# 20A-20.net
KiCad netlist of a schematic drawn in EAGLE
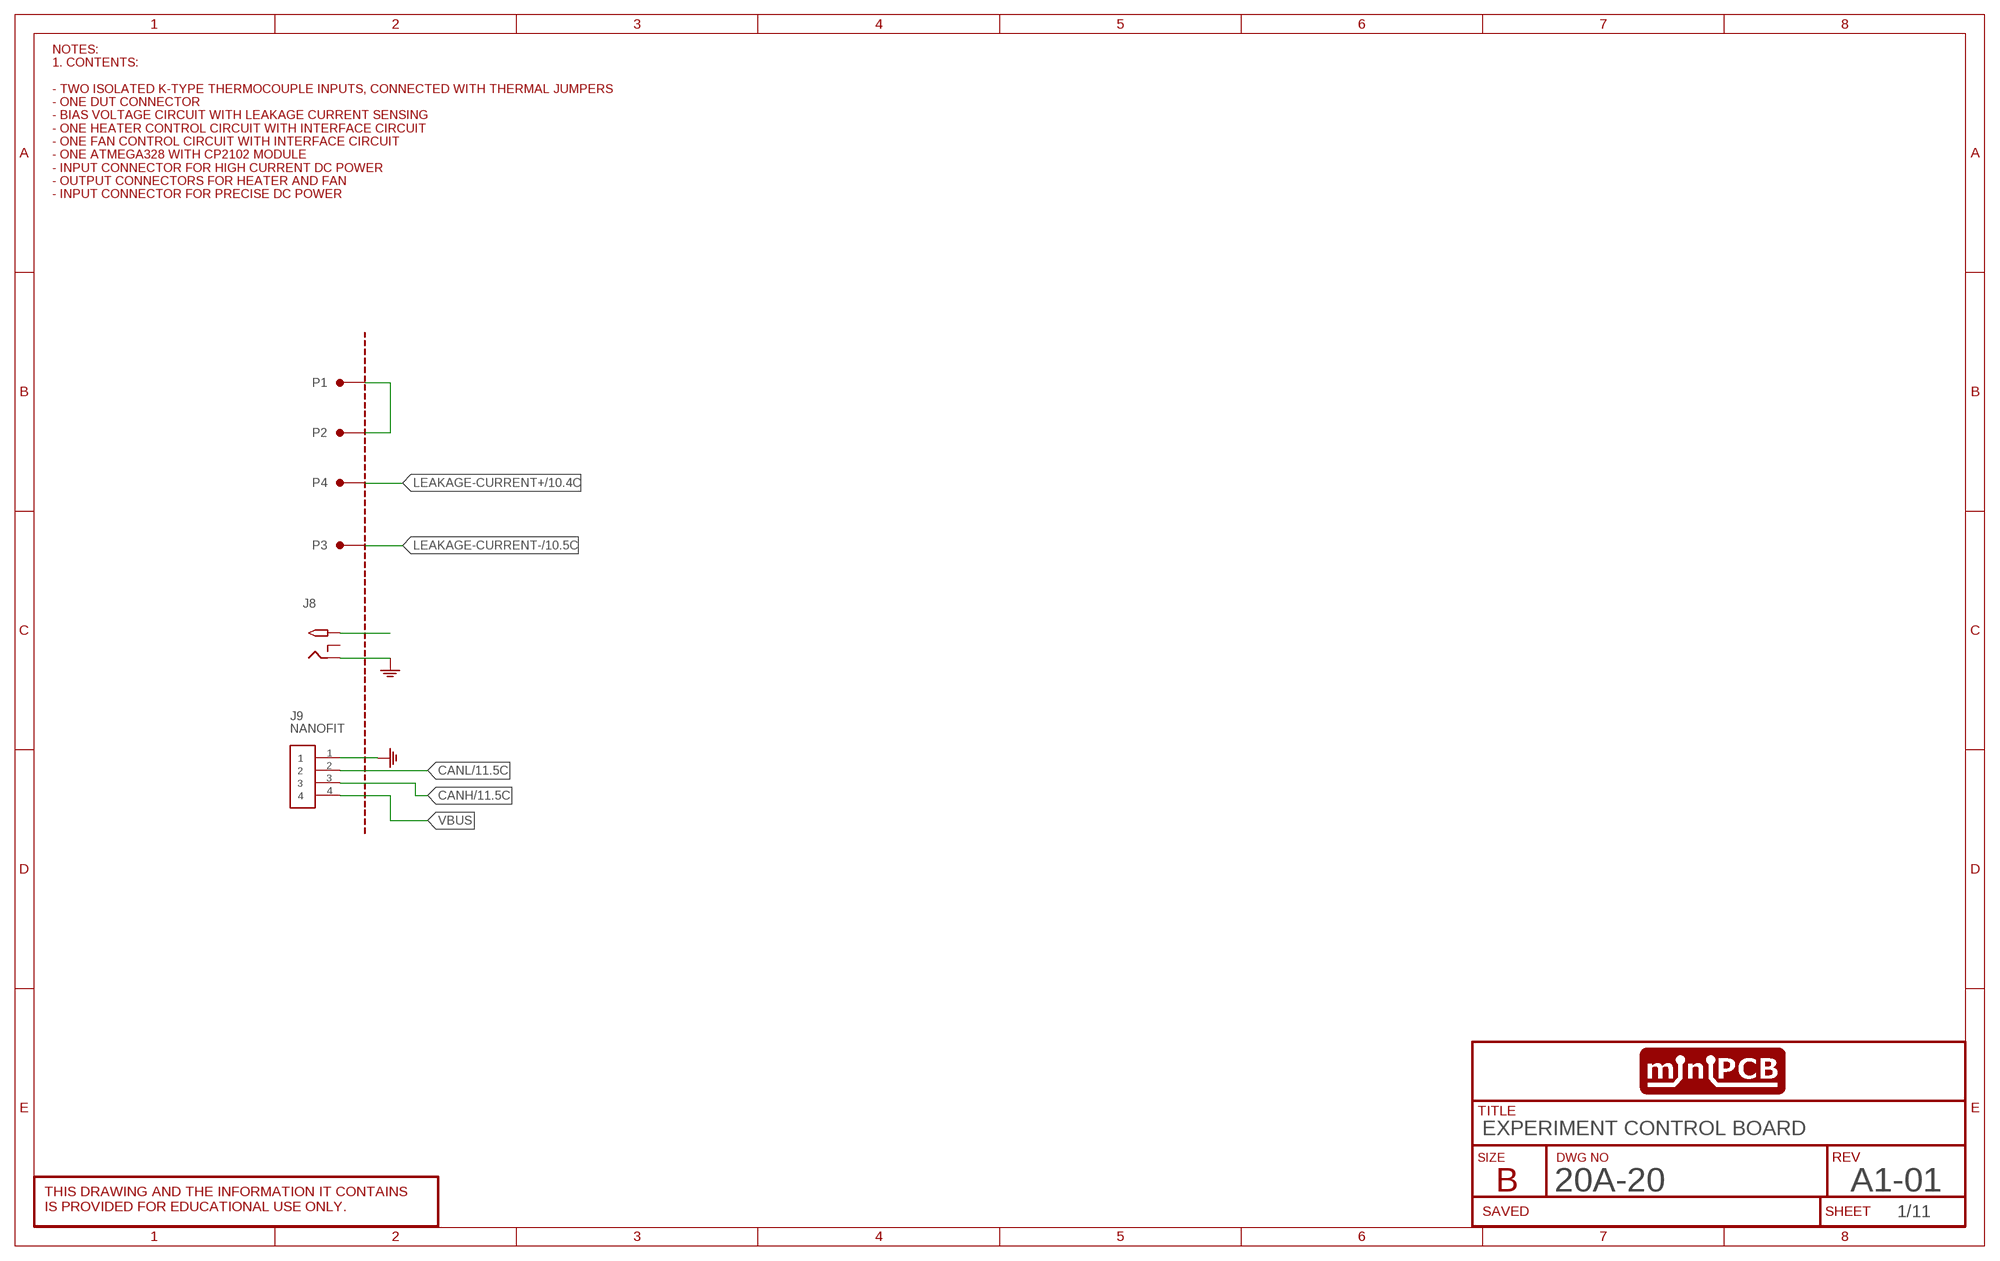
[diagram p0: schematic, sheet 1]
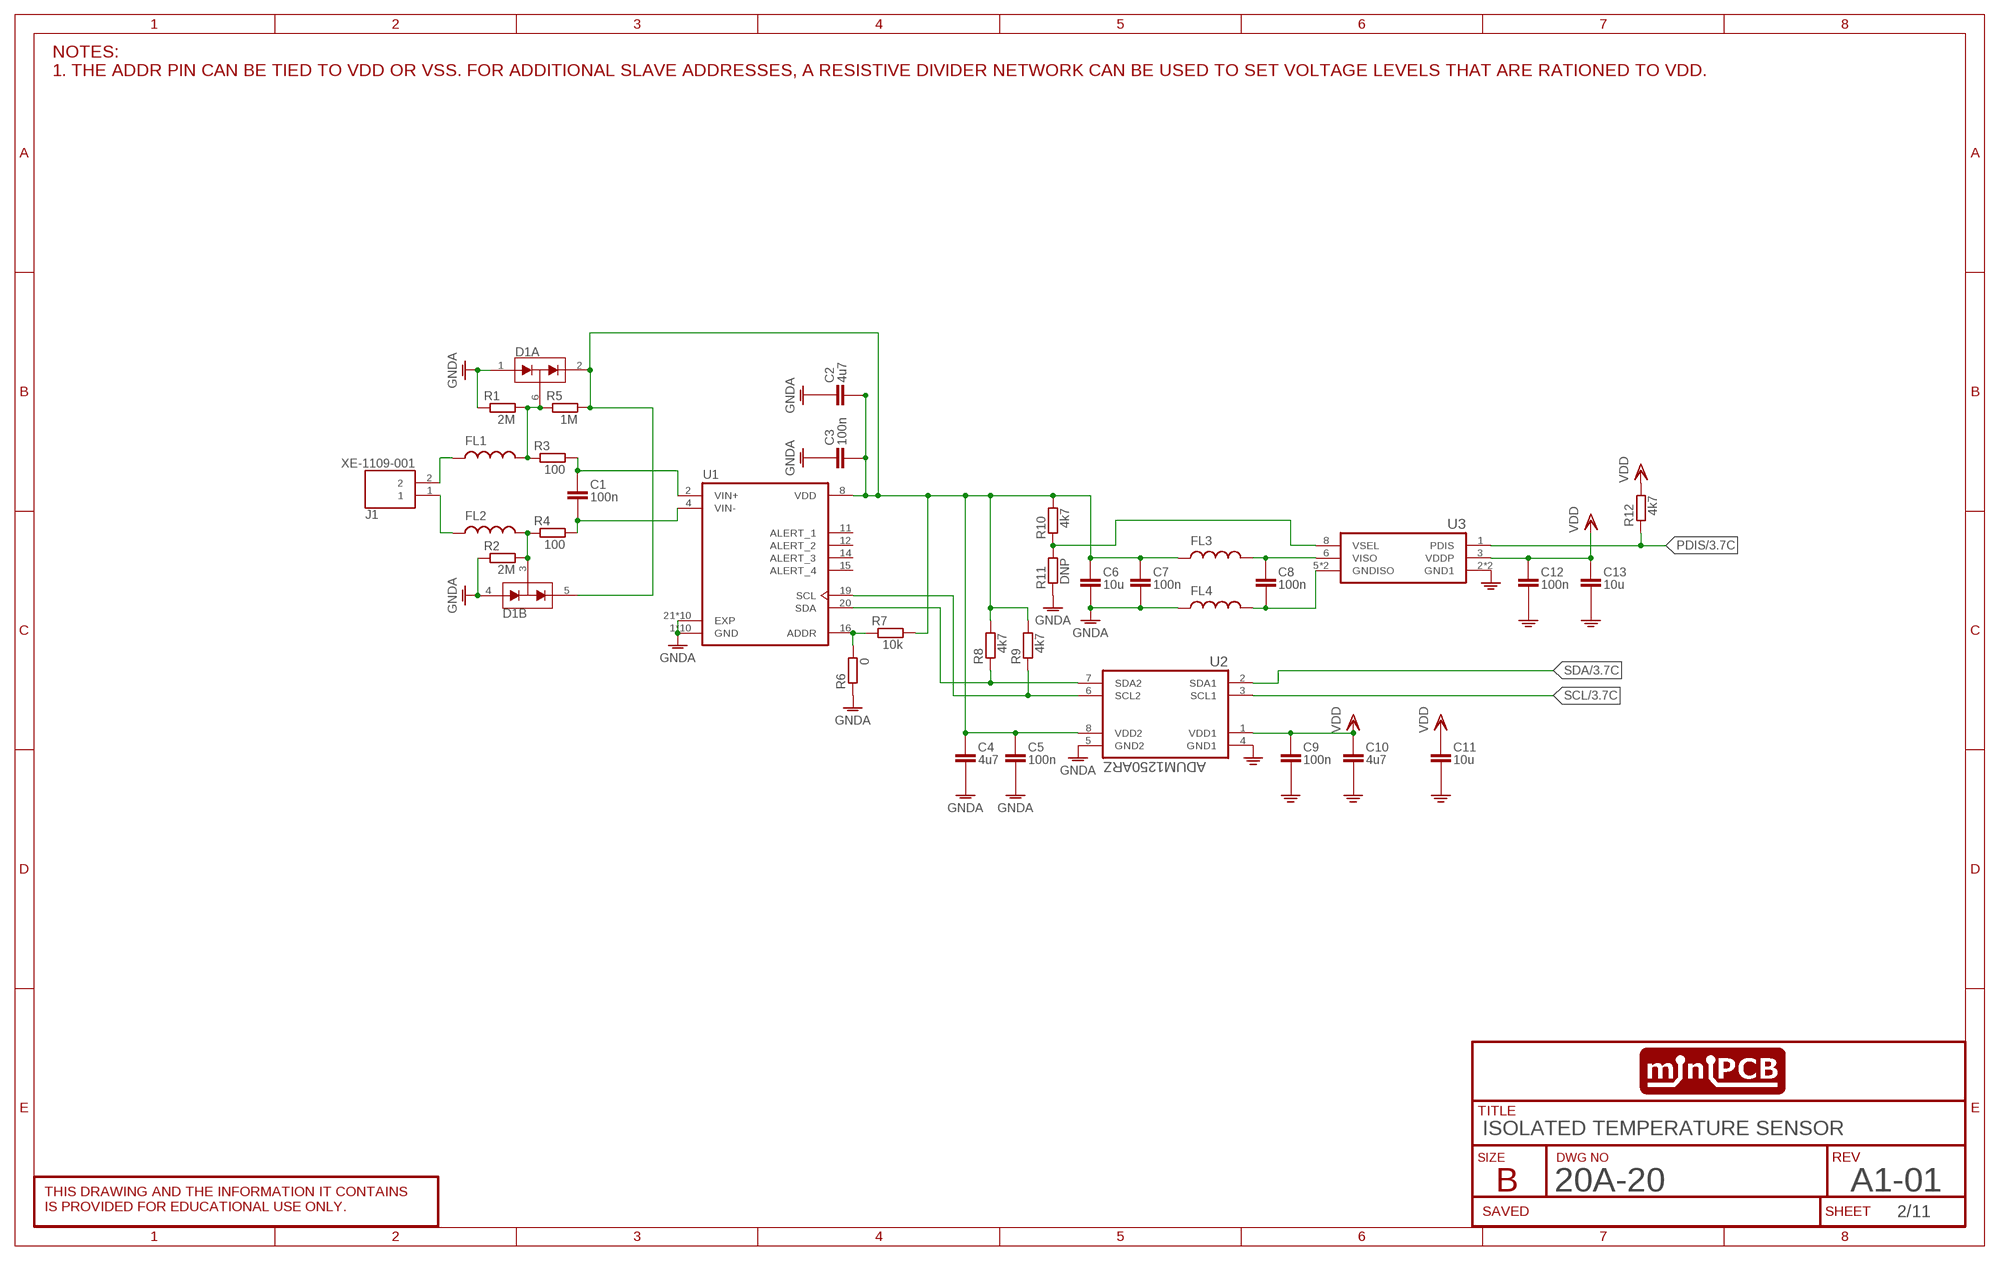
[diagram p1: schematic, sheet 2]
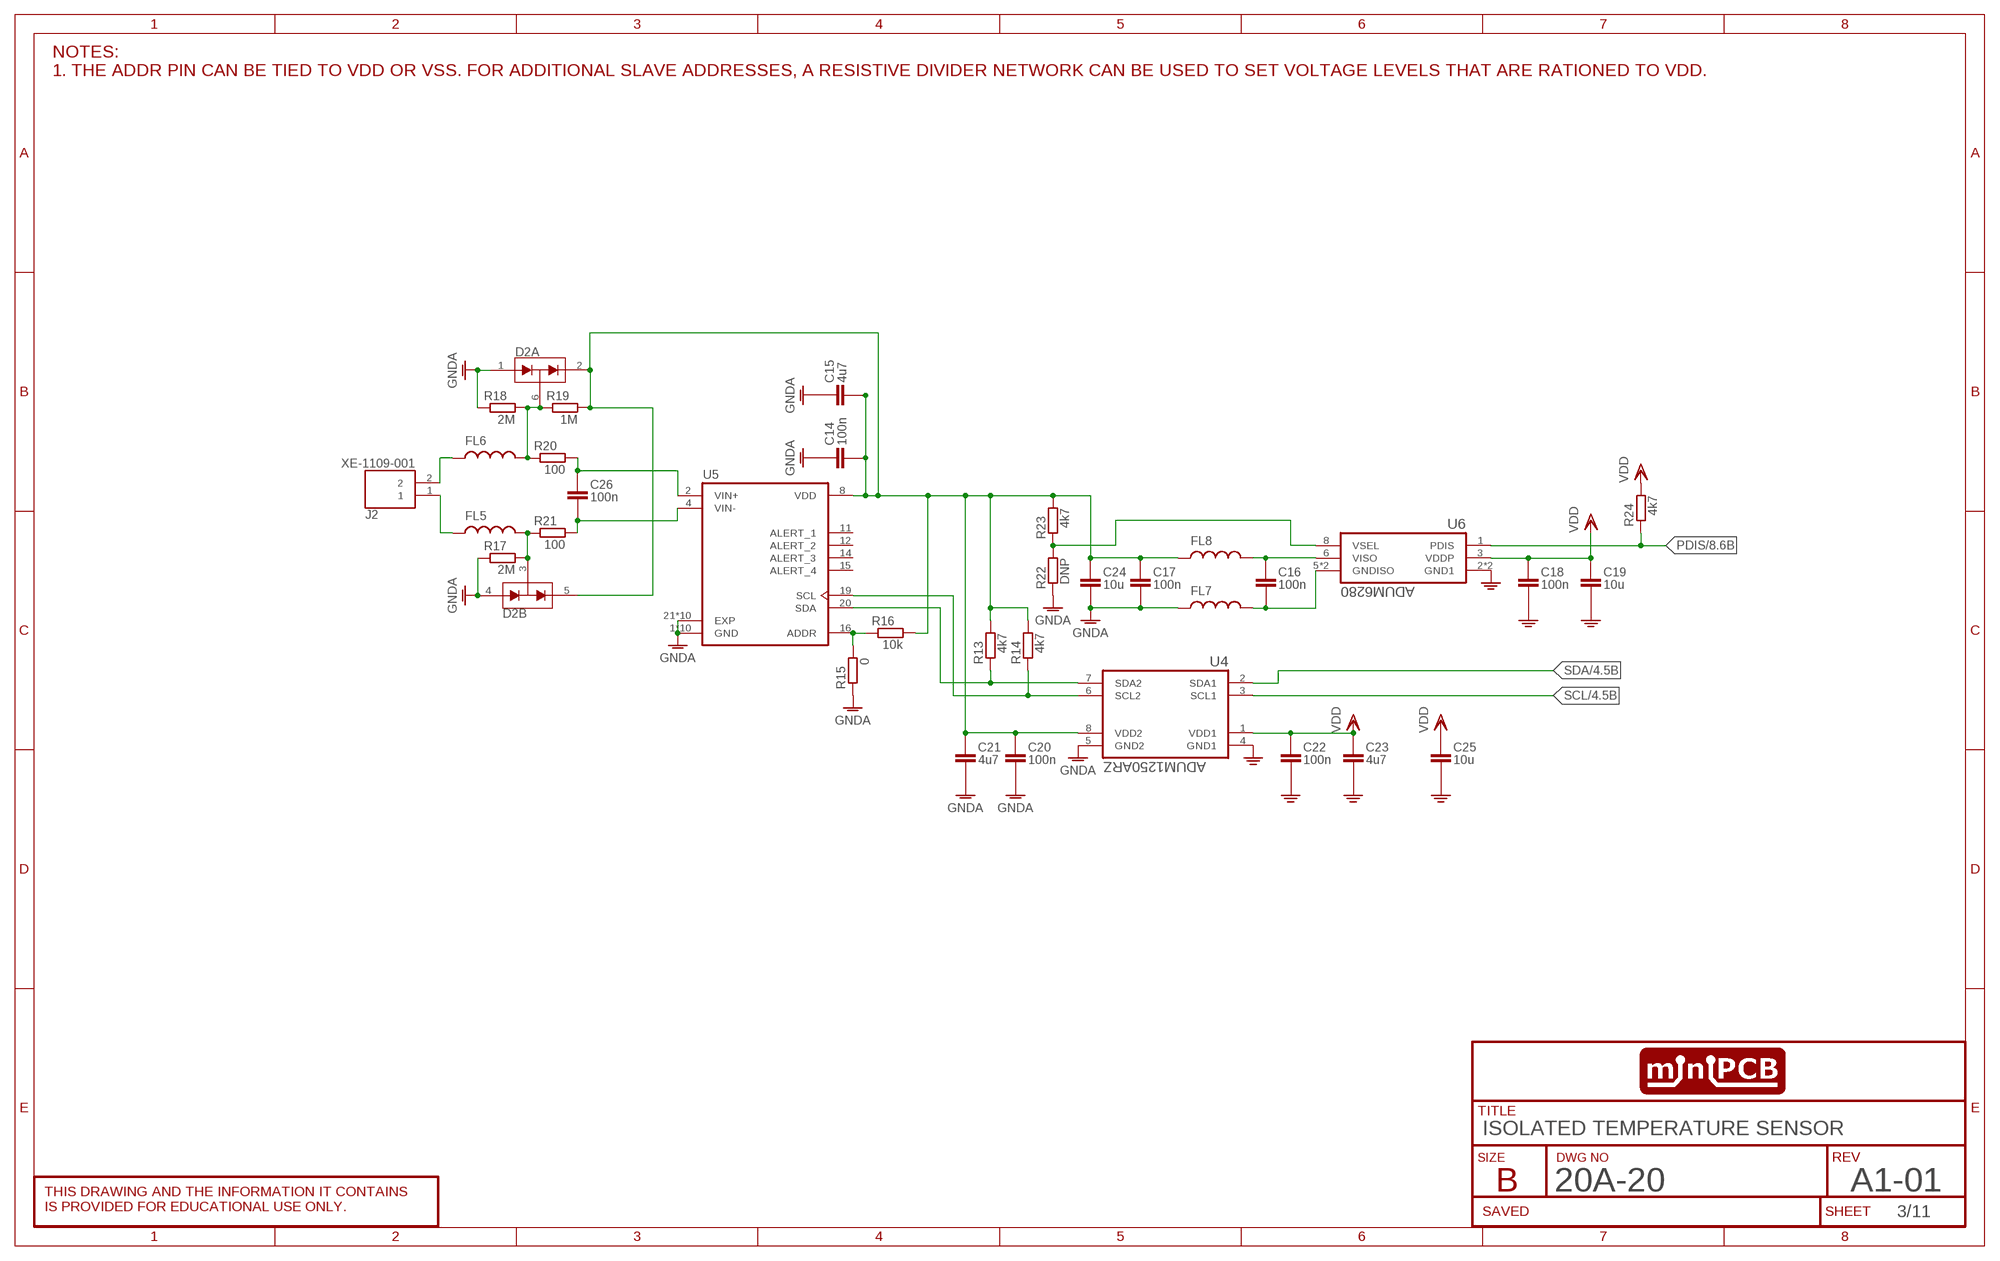
[diagram p2: schematic, sheet 3]
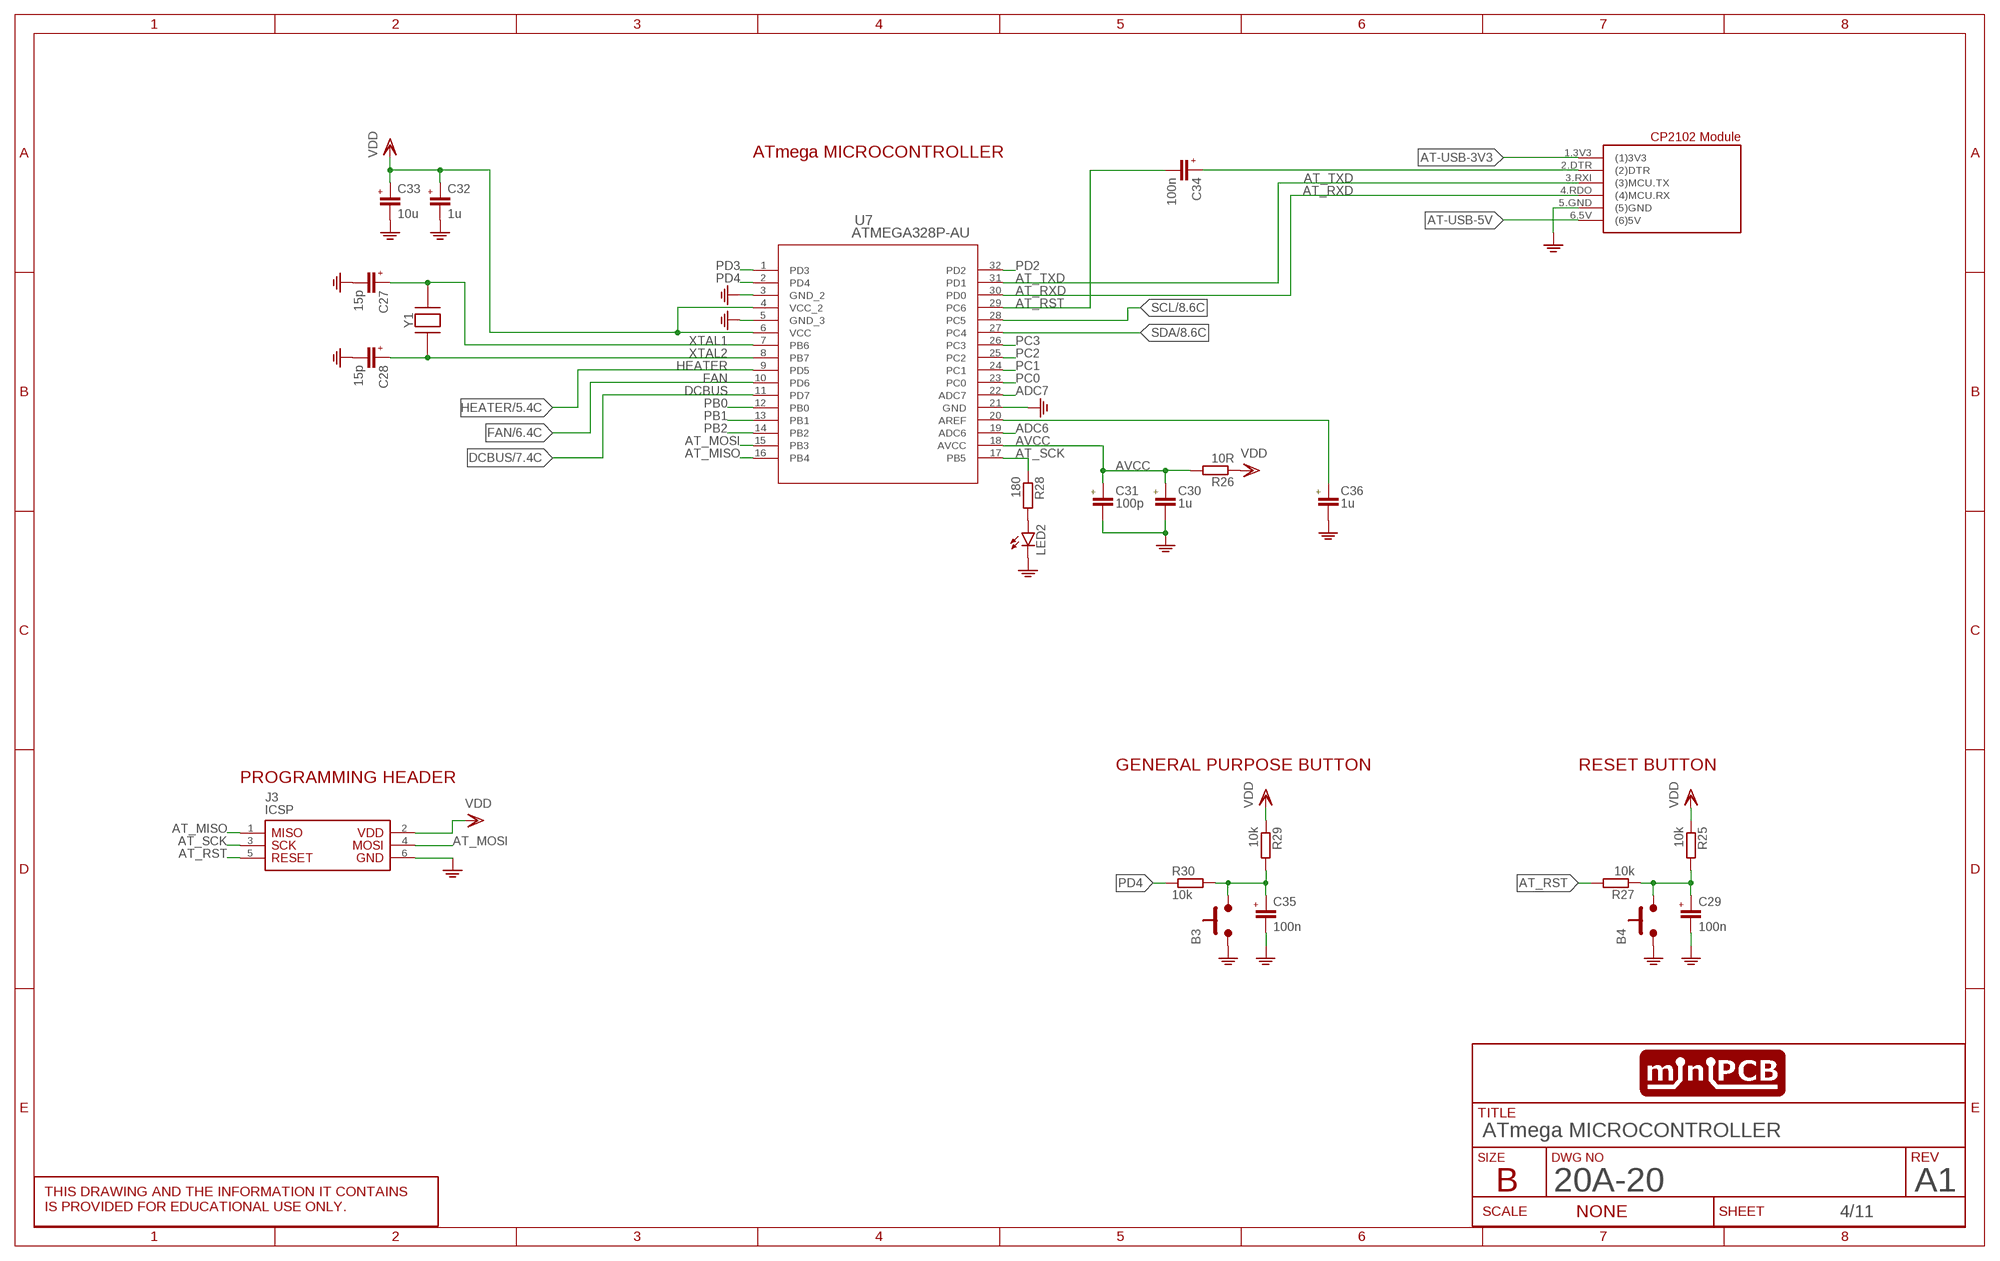
[diagram p3: schematic, sheet 4]
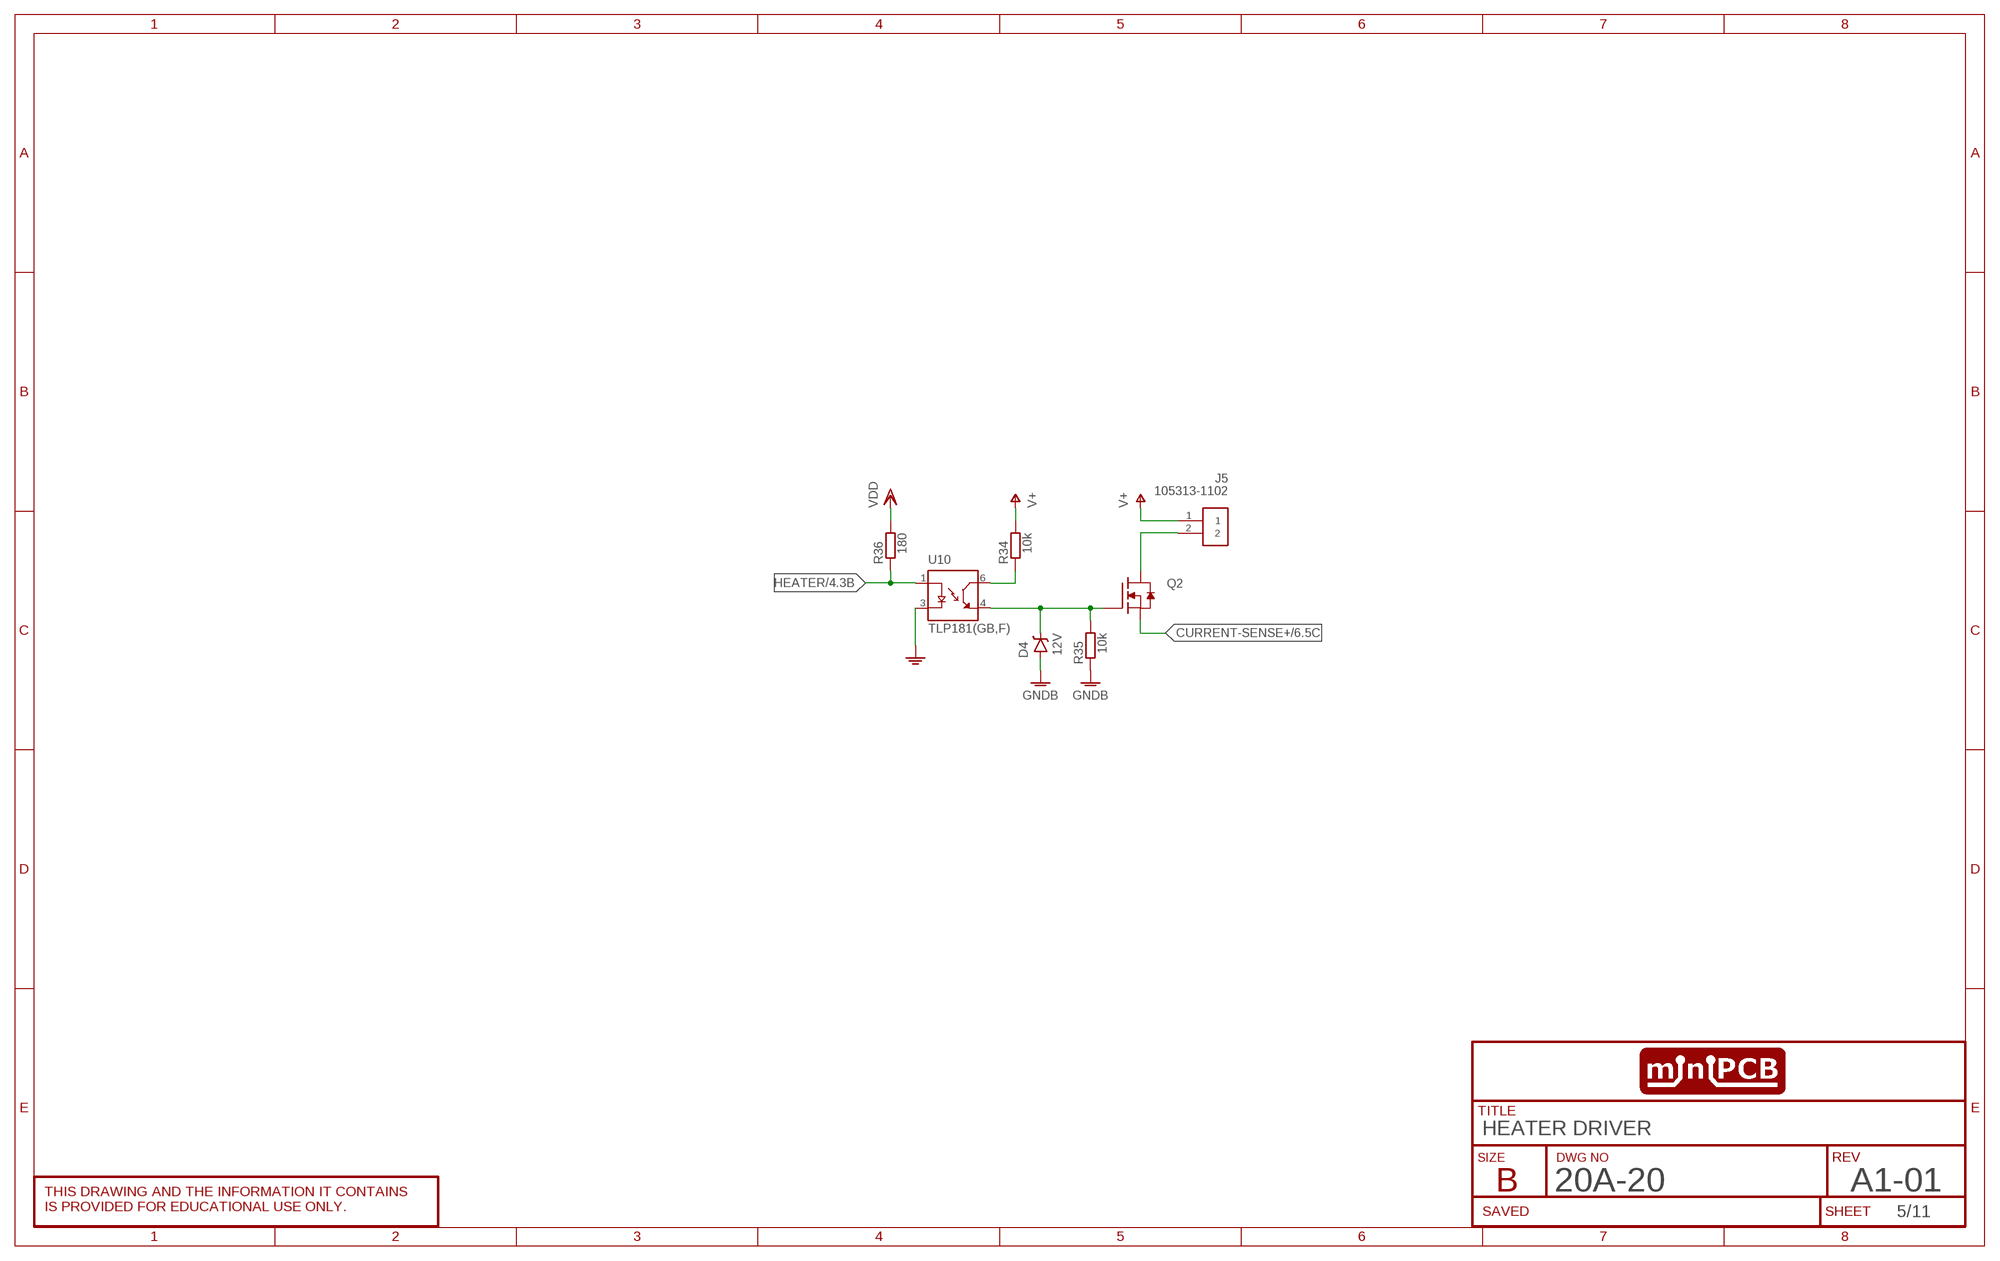
[diagram p4: schematic, sheet 5]
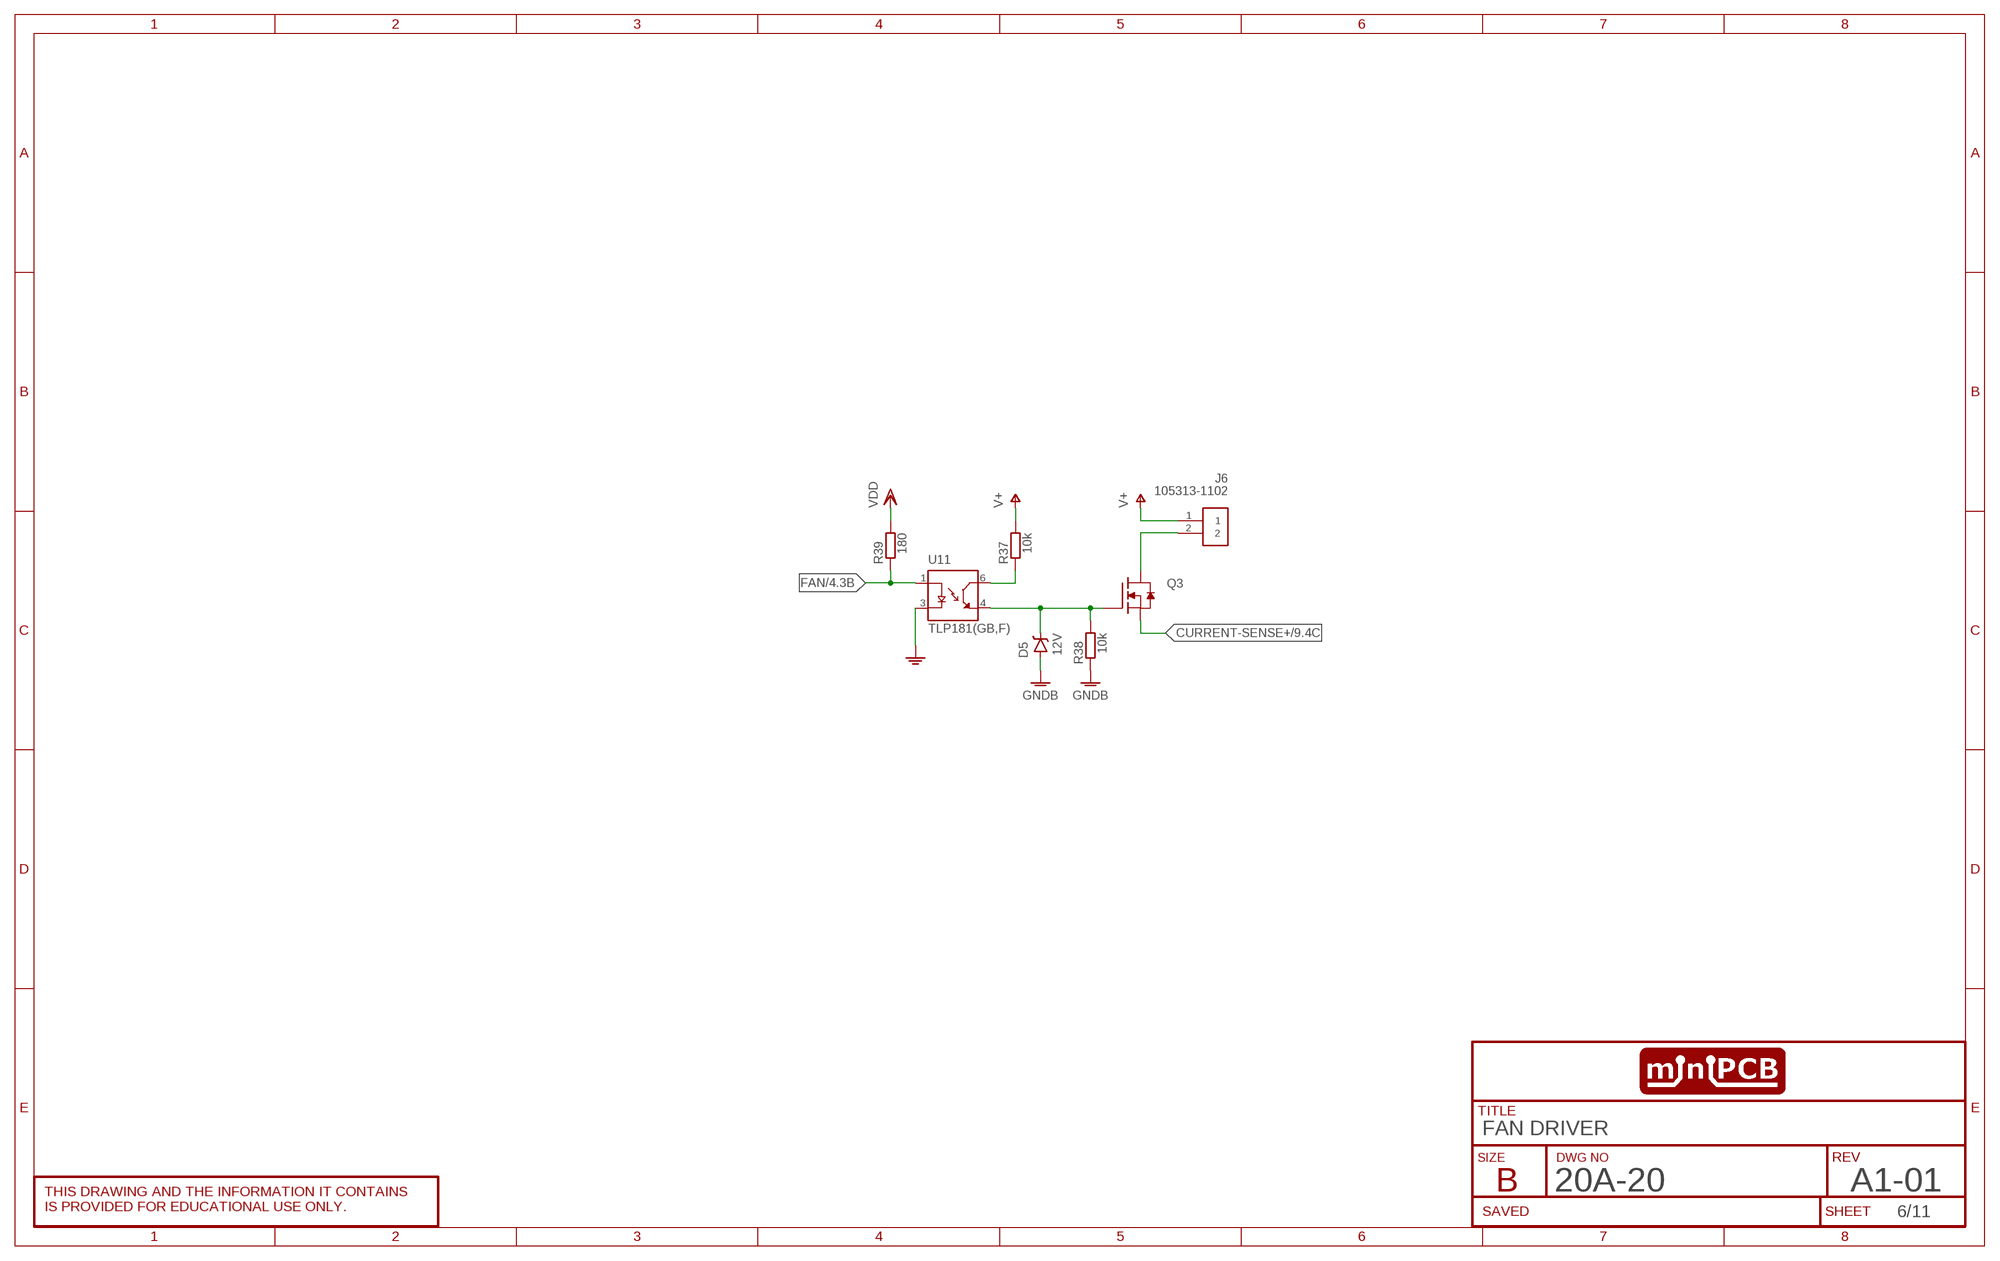
[diagram p5: schematic, sheet 6]
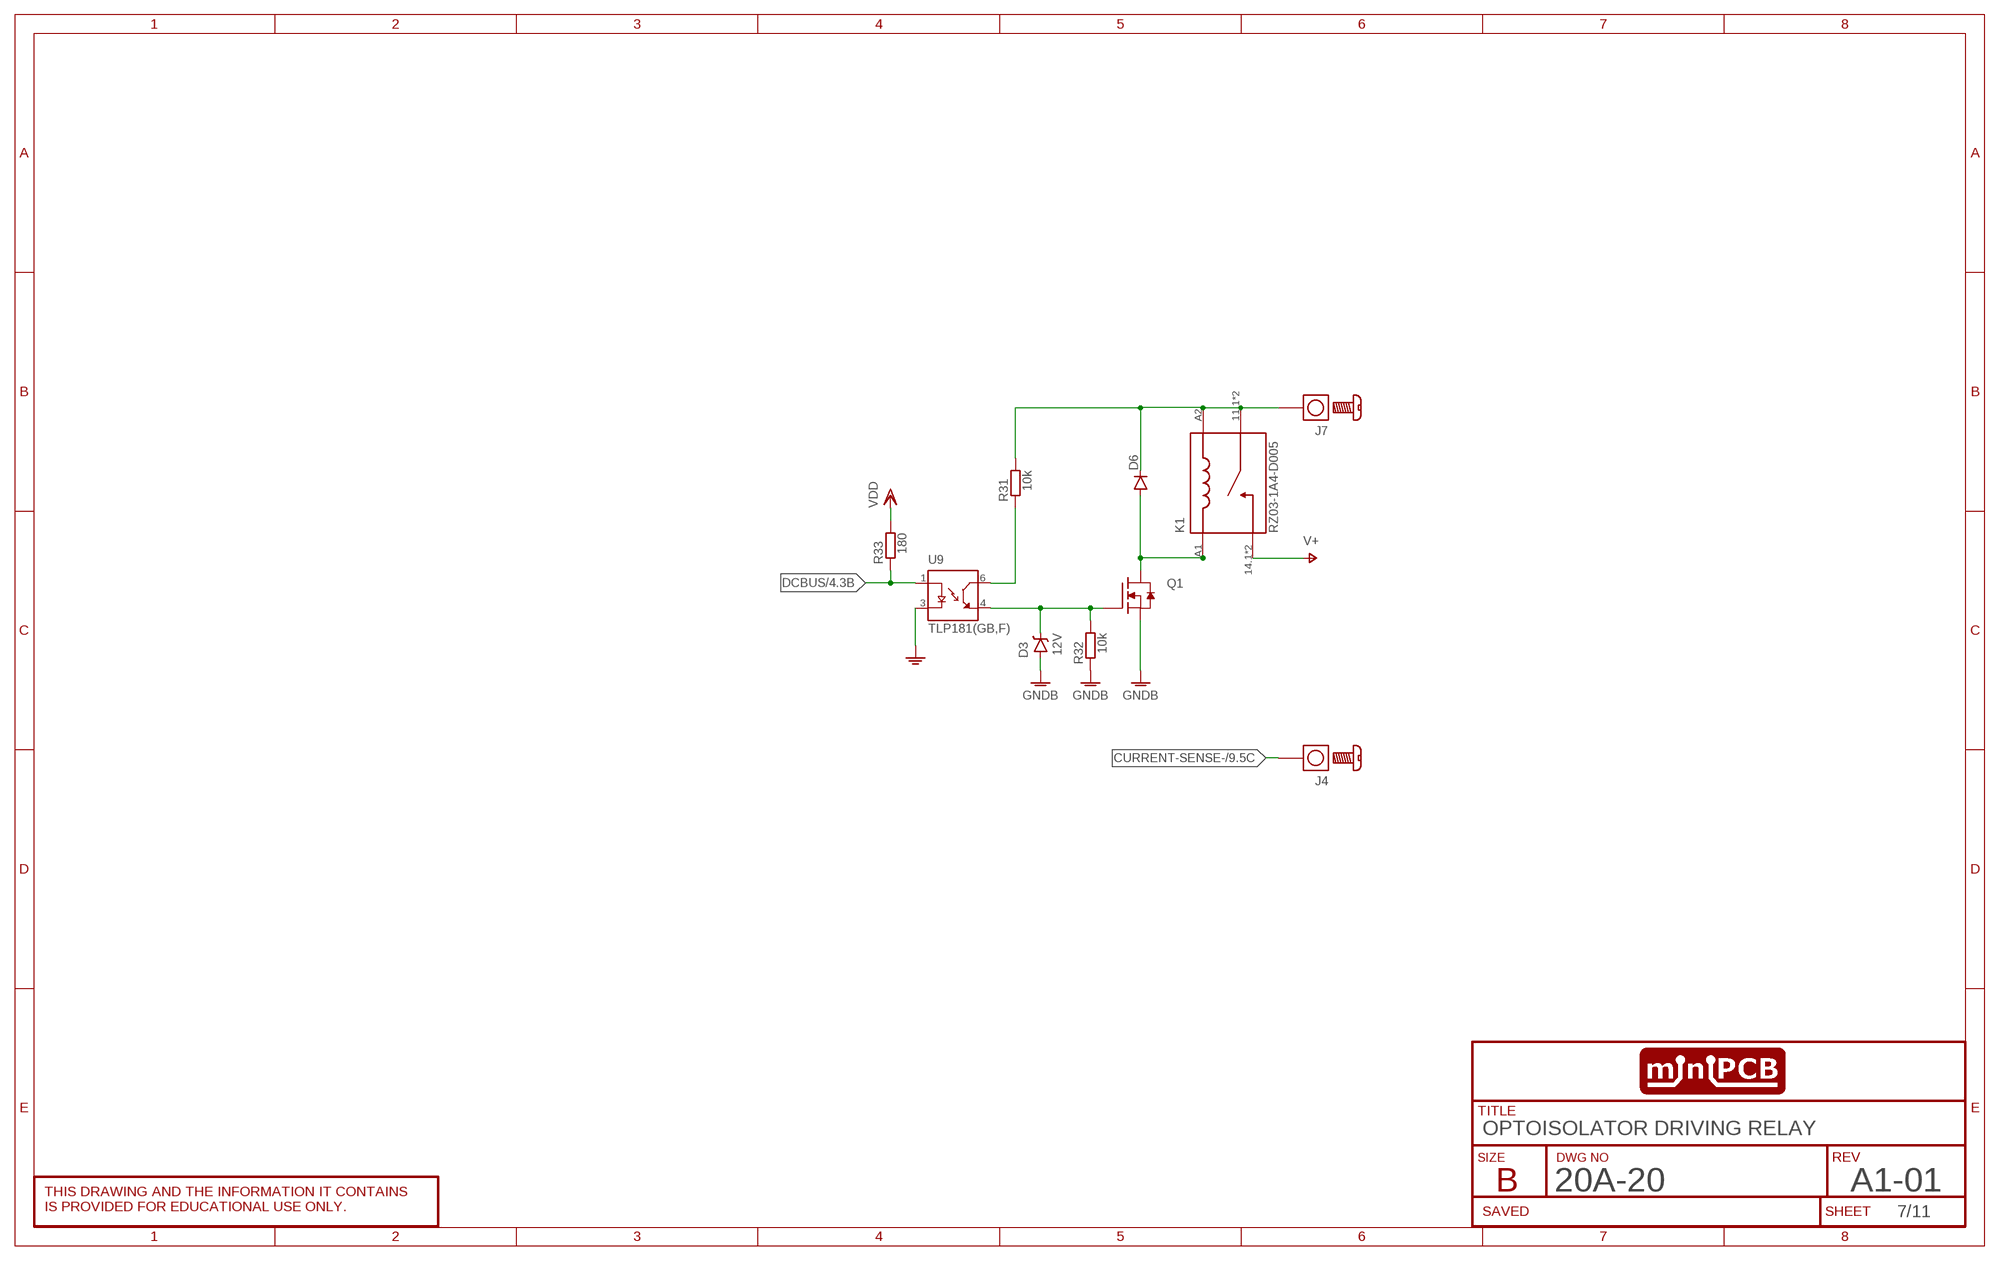
[diagram p6: schematic, sheet 7]
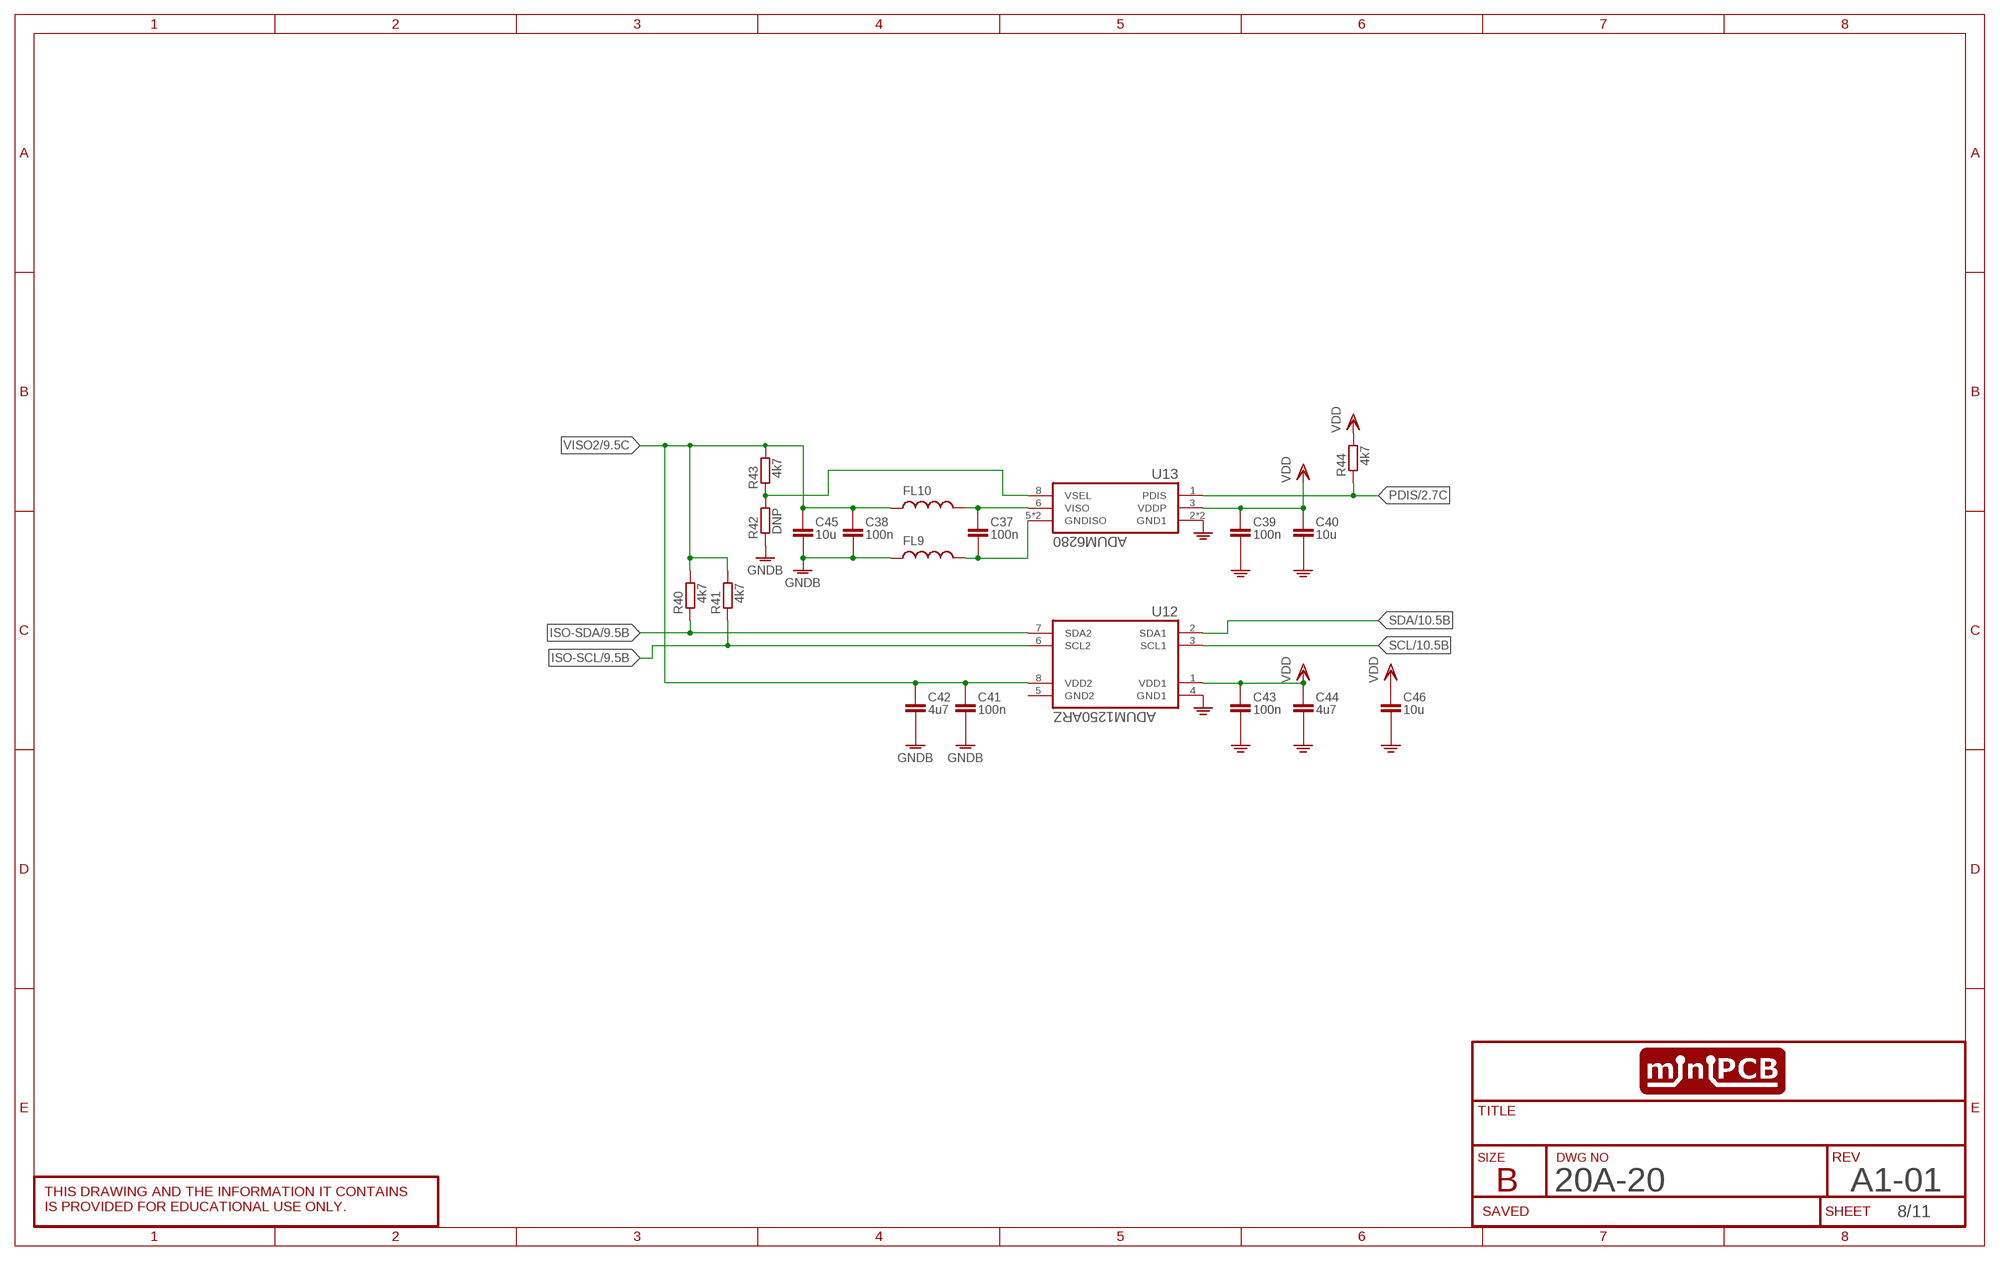
[diagram p7: schematic, sheet 8]
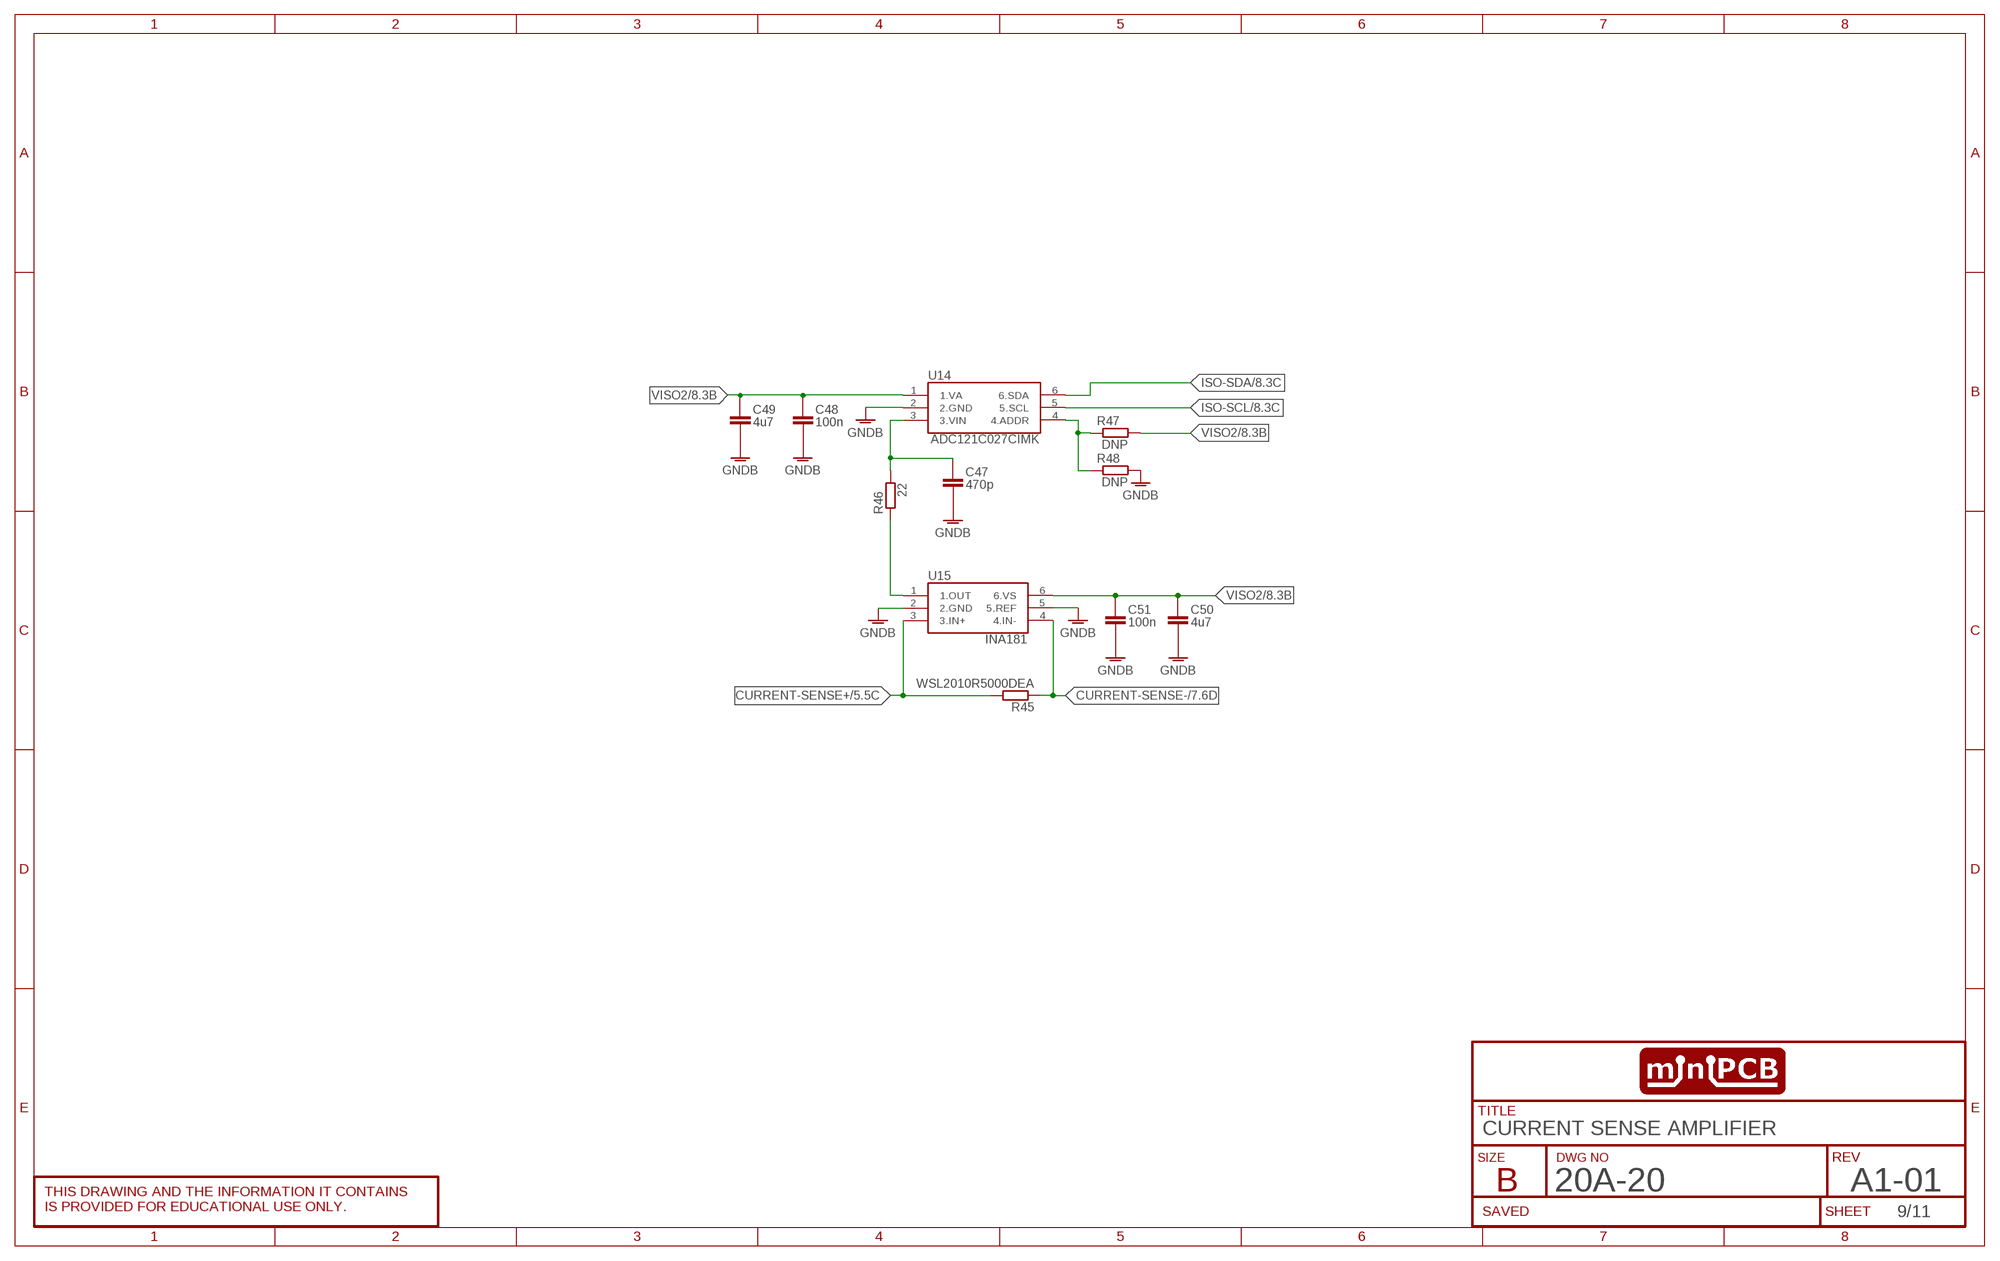
[diagram p8: schematic, sheet 9]
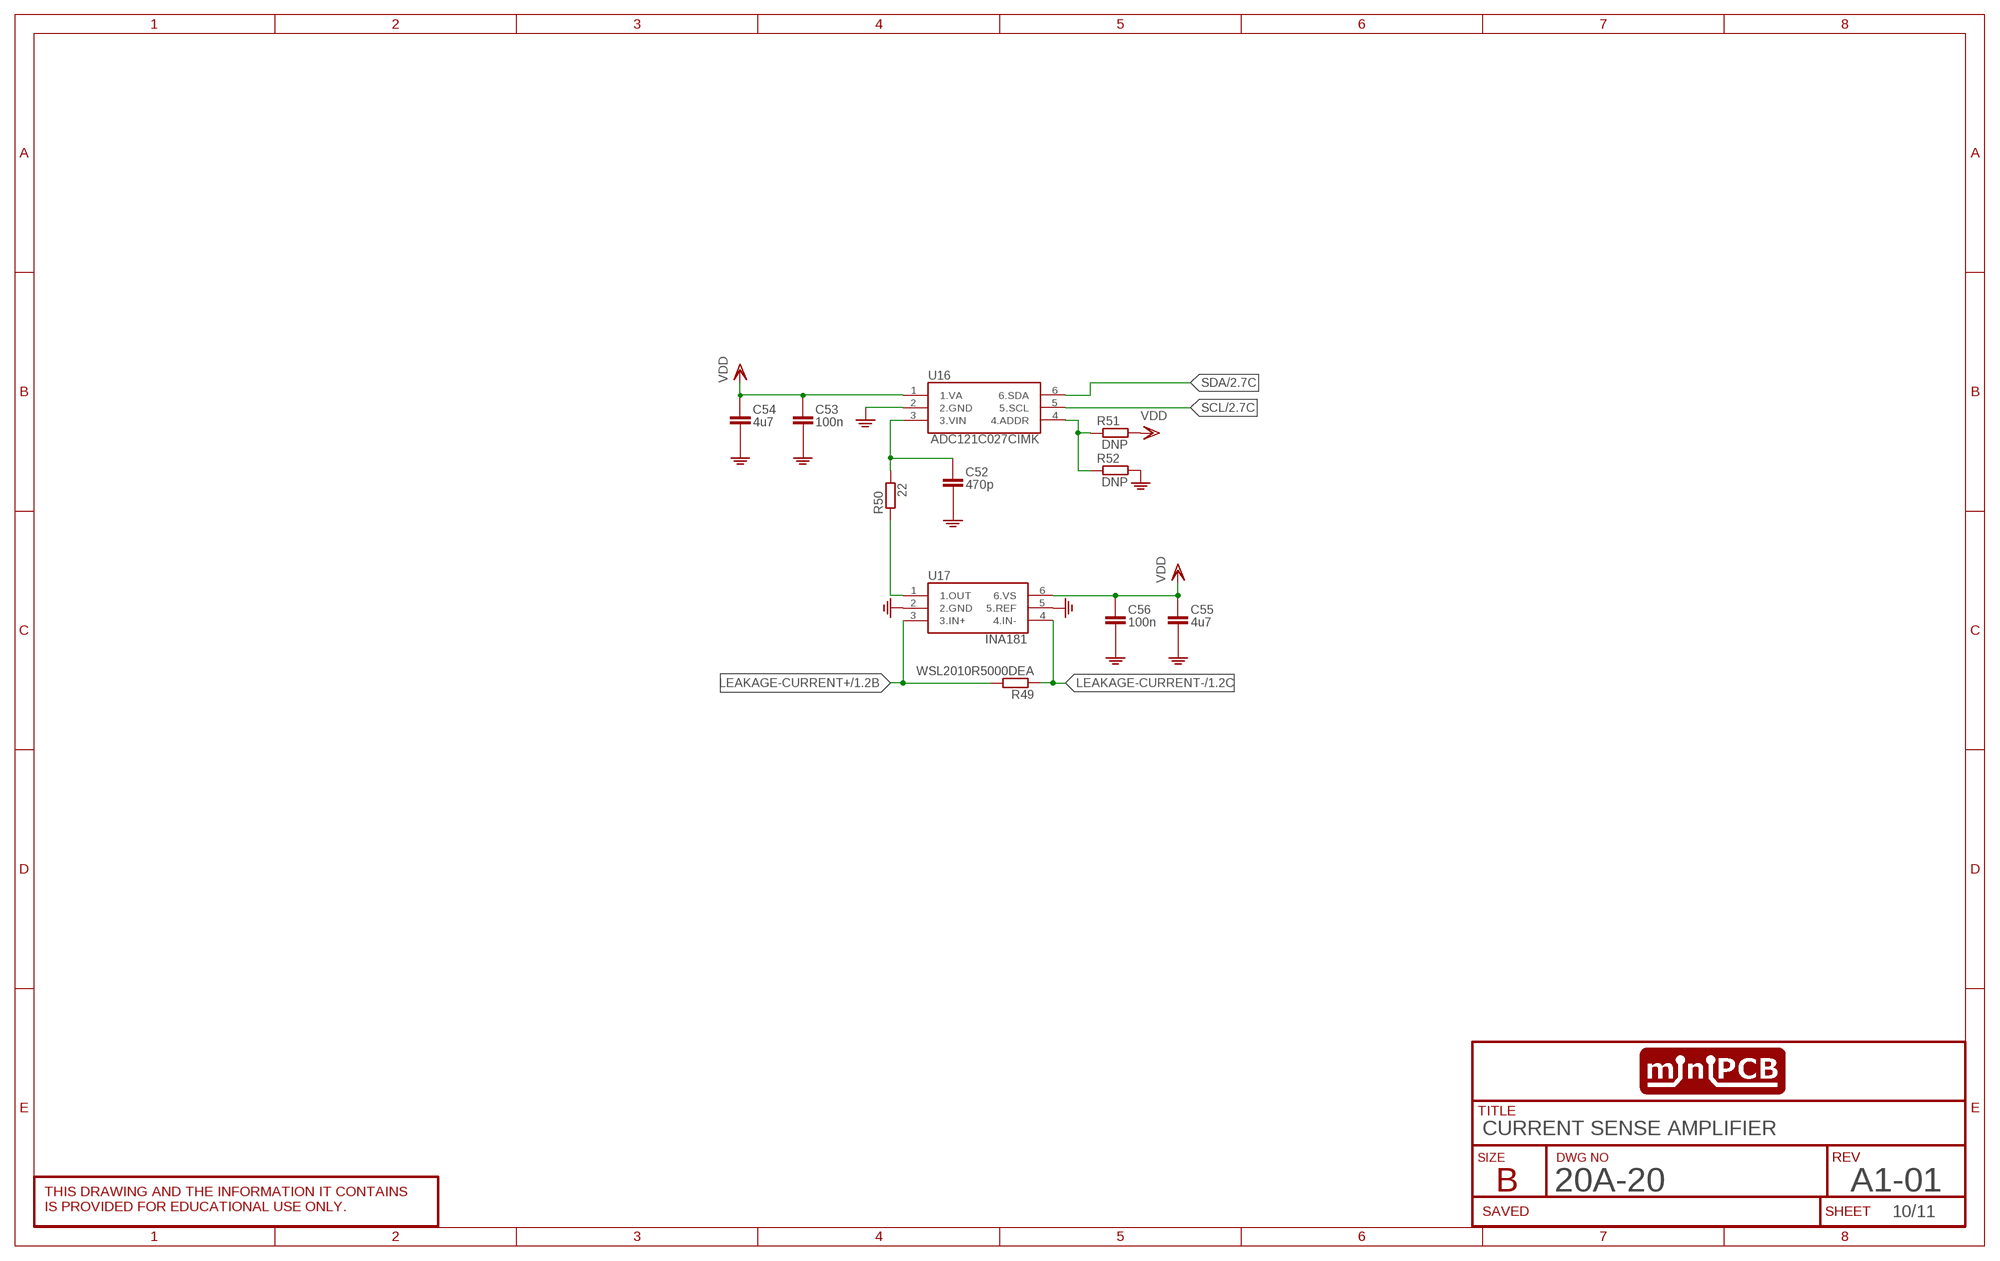
[diagram p9: schematic, sheet 10]
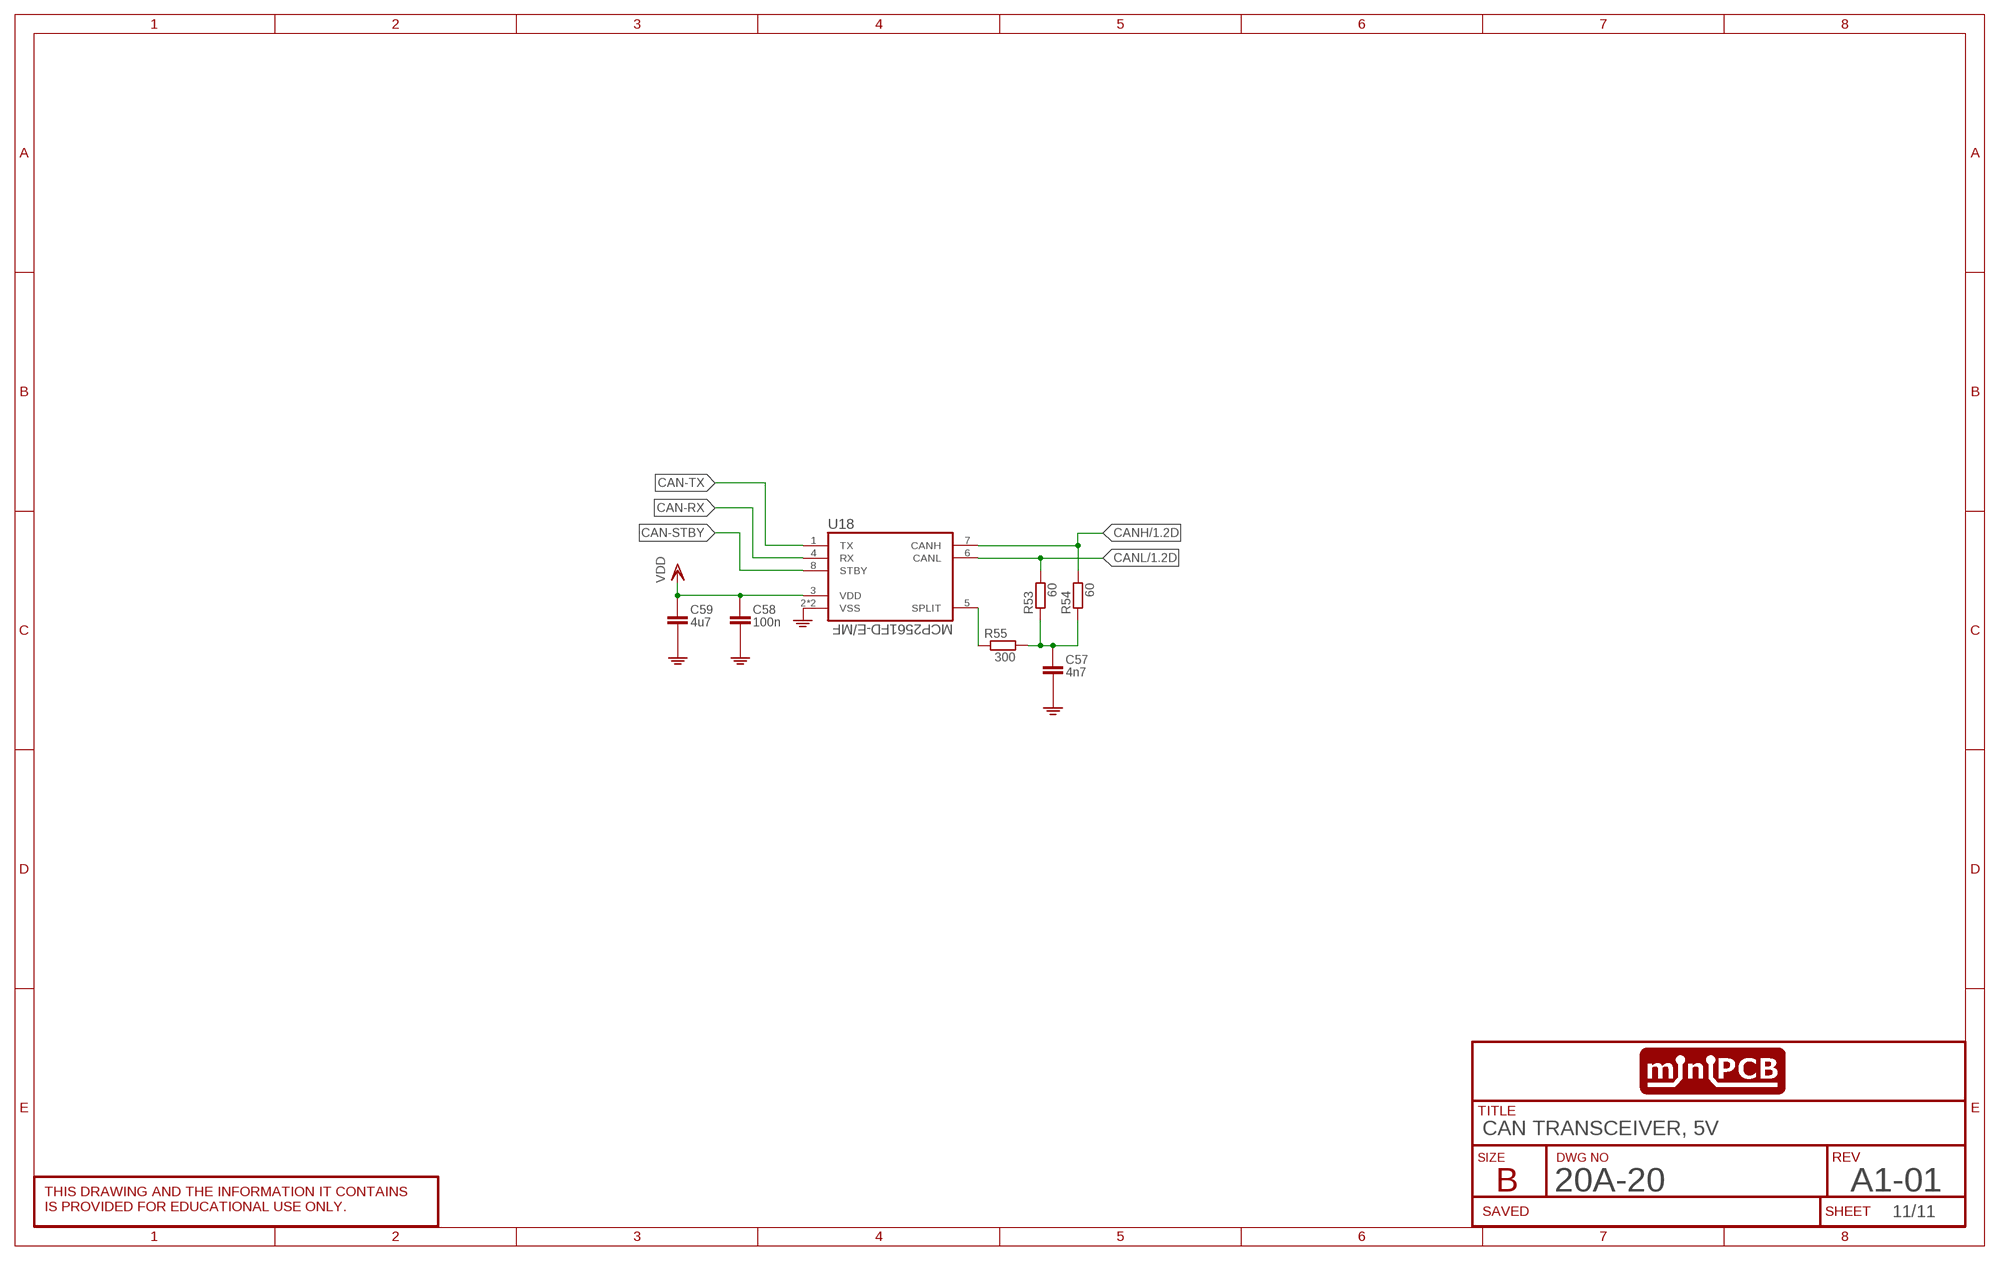
[diagram p10: schematic, sheet 11]

(export (version "E")
  (design (tool "Eeschema 10.0.6"))
  (components
    (comp (ref "D5")
      (value "12V")
      (footprint "eagle-import:SOT23")
      (libsource (lib "eagle-import") (part "ZENERSOT23"))
    )
    (comp (ref "J6")
      (value "105313-1102")
      (footprint "eagle-import:PINS_2-NANOFIT-H")
      (libsource (lib "eagle-import") (part "PINS_2-NANOFIT-105313-1102"))
    )
    (comp (ref "Q3")
      (value "MOSFET-NDPAK")
      (footprint "eagle-import:DPACK")
      (libsource (lib "eagle-import") (part "MOSFET-NDPAK"))
    )
    (comp (ref "R37")
      (value "10k")
      (footprint "eagle-import:R0805")
      (libsource (lib "eagle-import") (part "RESISTORSMD"))
    )
    (comp (ref "R38")
      (value "10k")
      (footprint "eagle-import:R0805")
      (libsource (lib "eagle-import") (part "RESISTORSMD"))
    )
    (comp (ref "R39")
      (value "180")
      (footprint "eagle-import:R0805")
      (libsource (lib "eagle-import") (part "RESISTORSMD"))
    )
    (comp (ref "U11")
      (value "TLP181(GB,F)")
      (footprint "eagle-import:SOIC254P700X280-4N")
      (fields (field (name "MF") "Toshiba"))
      (libsource (lib "eagle-import") (part "TLP181(GB,F)"))
    )
    (comp (ref "C1")
      (value "100n")
      (footprint "eagle-import:C0402")
      (libsource (lib "eagle-import") (part "CAPACITOR0402"))
    )
    (comp (ref "C2")
      (value "4u7")
      (footprint "eagle-import:C0402")
      (libsource (lib "eagle-import") (part "CAPACITOR0402"))
    )
    (comp (ref "C3")
      (value "100n")
      (footprint "eagle-import:C0402")
      (libsource (lib "eagle-import") (part "CAPACITOR0402"))
    )
    (comp (ref "C4")
      (value "4u7")
      (footprint "eagle-import:C0402")
      (libsource (lib "eagle-import") (part "CAPACITOR0402"))
    )
    (comp (ref "C5")
      (value "100n")
      (footprint "eagle-import:C0402")
      (libsource (lib "eagle-import") (part "CAPACITOR0402"))
    )
    (comp (ref "C6")
      (value "10u")
      (footprint "eagle-import:C0805")
      (libsource (lib "eagle-import") (part "CAPACITORSMD"))
    )
    (comp (ref "C7")
      (value "100n")
      (footprint "eagle-import:C0402")
      (libsource (lib "eagle-import") (part "CAPACITOR0402"))
    )
    (comp (ref "C8")
      (value "100n")
      (footprint "eagle-import:C0402")
      (libsource (lib "eagle-import") (part "CAPACITOR0402"))
    )
    (comp (ref "C9")
      (value "100n")
      (footprint "eagle-import:C0402")
      (libsource (lib "eagle-import") (part "CAPACITOR0402"))
    )
    (comp (ref "C10")
      (value "4u7")
      (footprint "eagle-import:C0402")
      (libsource (lib "eagle-import") (part "CAPACITOR0402"))
    )
    (comp (ref "C11")
      (value "10u")
      (footprint "eagle-import:C0805")
      (libsource (lib "eagle-import") (part "CAPACITORSMD"))
    )
    (comp (ref "C12")
      (value "100n")
      (footprint "eagle-import:C0402")
      (libsource (lib "eagle-import") (part "CAPACITOR0402"))
    )
    (comp (ref "C13")
      (value "10u")
      (footprint "eagle-import:C0805")
      (libsource (lib "eagle-import") (part "CAPACITORSMD"))
    )
    (comp (ref "D1")
      (value "SDA004-7")
      (footprint "eagle-import:SOT363")
      (libsource (lib "eagle-import") (part "SDA004-7"))
    )
    (comp (ref "FL1")
      (value "BLM03HG601SZ1D")
      (footprint "eagle-import:R0402")
      (libsource (lib "eagle-import") (part "BLM03HG601SZ1D"))
    )
    (comp (ref "FL2")
      (value "BLM03HG601SZ1D")
      (footprint "eagle-import:R0402")
      (libsource (lib "eagle-import") (part "BLM03HG601SZ1D"))
    )
    (comp (ref "FL3")
      (value "BLM03HG601SZ1D")
      (footprint "eagle-import:R0402")
      (libsource (lib "eagle-import") (part "BLM03HG601SZ1D"))
    )
    (comp (ref "FL4")
      (value "BLM03HG601SZ1D")
      (footprint "eagle-import:R0402")
      (libsource (lib "eagle-import") (part "BLM03HG601SZ1D"))
    )
    (comp (ref "J1")
      (value "XE-1109-001")
      (footprint "eagle-import:XE-1109-001")
      (libsource (lib "eagle-import") (part "XE-1109-001"))
    )
    (comp (ref "R1")
      (value "2M")
      (footprint "eagle-import:R0402")
      (libsource (lib "eagle-import") (part "RESISTOR0402"))
    )
    (comp (ref "R2")
      (value "2M")
      (footprint "eagle-import:R0402")
      (libsource (lib "eagle-import") (part "RESISTOR0402"))
    )
    (comp (ref "R3")
      (value "100")
      (footprint "eagle-import:R0402")
      (libsource (lib "eagle-import") (part "RESISTOR0402"))
    )
    (comp (ref "R4")
      (value "100")
      (footprint "eagle-import:R0402")
      (libsource (lib "eagle-import") (part "RESISTOR0402"))
    )
    (comp (ref "R5")
      (value "1M")
      (footprint "eagle-import:R0402")
      (libsource (lib "eagle-import") (part "RESISTOR0402"))
    )
    (comp (ref "R6")
      (value "0")
      (footprint "eagle-import:R0402")
      (libsource (lib "eagle-import") (part "RESISTOR0402"))
    )
    (comp (ref "R7")
      (value "10k")
      (footprint "eagle-import:R0402")
      (libsource (lib "eagle-import") (part "RESISTOR0402"))
    )
    (comp (ref "R8")
      (value "4k7")
      (footprint "eagle-import:R0402")
      (libsource (lib "eagle-import") (part "RESISTOR0402"))
    )
    (comp (ref "R9")
      (value "4k7")
      (footprint "eagle-import:R0402")
      (libsource (lib "eagle-import") (part "RESISTOR0402"))
    )
    (comp (ref "R10")
      (value "4k7")
      (footprint "eagle-import:R0402")
      (libsource (lib "eagle-import") (part "RESISTOR0402"))
    )
    (comp (ref "R11")
      (value "DNP")
      (footprint "eagle-import:R0402")
      (libsource (lib "eagle-import") (part "RESISTOR0402"))
    )
    (comp (ref "R12")
      (value "4k7")
      (footprint "eagle-import:R0402")
      (libsource (lib "eagle-import") (part "RESISTOR0402"))
    )
    (comp (ref "U1")
      (value "MCP9600T-I/MX")
      (footprint "eagle-import:QFN65P500X500X100-21N_MCP9600T-I_MX")
      (fields (field (name "MF") "Microchip Technology"))
      (libsource (lib "eagle-import") (part "MCP9600T-I/MX"))
    )
    (comp (ref "U2")
      (value "ADUM1250ARZ")
      (footprint "eagle-import:SOIC127P600X175-8N")
      (fields (field (name "MF") "Analog Devices"))
      (libsource (lib "eagle-import") (part "ADUM1250ARZ"))
    )
    (comp (ref "U3")
      (value "ADUM6280")
      (footprint "eagle-import:SOIC127P600X175-8N")
      (libsource (lib "eagle-import") (part "ADUM6280"))
    )
    (comp (ref "C14")
      (value "100n")
      (footprint "eagle-import:C0402")
      (libsource (lib "eagle-import") (part "CAPACITOR0402"))
    )
    (comp (ref "C15")
      (value "4u7")
      (footprint "eagle-import:C0402")
      (libsource (lib "eagle-import") (part "CAPACITOR0402"))
    )
    (comp (ref "C16")
      (value "100n")
      (footprint "eagle-import:C0402")
      (libsource (lib "eagle-import") (part "CAPACITOR0402"))
    )
    (comp (ref "C17")
      (value "100n")
      (footprint "eagle-import:C0402")
      (libsource (lib "eagle-import") (part "CAPACITOR0402"))
    )
    (comp (ref "C18")
      (value "100n")
      (footprint "eagle-import:C0402")
      (libsource (lib "eagle-import") (part "CAPACITOR0402"))
    )
    (comp (ref "C19")
      (value "10u")
      (footprint "eagle-import:C0805")
      (libsource (lib "eagle-import") (part "CAPACITORSMD"))
    )
    (comp (ref "C20")
      (value "100n")
      (footprint "eagle-import:C0402")
      (libsource (lib "eagle-import") (part "CAPACITOR0402"))
    )
    (comp (ref "C21")
      (value "4u7")
      (footprint "eagle-import:C0402")
      (libsource (lib "eagle-import") (part "CAPACITOR0402"))
    )
    (comp (ref "C22")
      (value "100n")
      (footprint "eagle-import:C0402")
      (libsource (lib "eagle-import") (part "CAPACITOR0402"))
    )
    (comp (ref "C23")
      (value "4u7")
      (footprint "eagle-import:C0402")
      (libsource (lib "eagle-import") (part "CAPACITOR0402"))
    )
    (comp (ref "C24")
      (value "10u")
      (footprint "eagle-import:C0805")
      (libsource (lib "eagle-import") (part "CAPACITORSMD"))
    )
    (comp (ref "C25")
      (value "10u")
      (footprint "eagle-import:C0805")
      (libsource (lib "eagle-import") (part "CAPACITORSMD"))
    )
    (comp (ref "C26")
      (value "100n")
      (footprint "eagle-import:C0402")
      (libsource (lib "eagle-import") (part "CAPACITOR0402"))
    )
    (comp (ref "D2")
      (value "SDA004-7")
      (footprint "eagle-import:SOT363")
      (libsource (lib "eagle-import") (part "SDA004-7"))
    )
    (comp (ref "FL5")
      (value "BLM03HG601SZ1D")
      (footprint "eagle-import:R0402")
      (libsource (lib "eagle-import") (part "BLM03HG601SZ1D"))
    )
    (comp (ref "FL6")
      (value "BLM03HG601SZ1D")
      (footprint "eagle-import:R0402")
      (libsource (lib "eagle-import") (part "BLM03HG601SZ1D"))
    )
    (comp (ref "FL7")
      (value "BLM03HG601SZ1D")
      (footprint "eagle-import:R0402")
      (libsource (lib "eagle-import") (part "BLM03HG601SZ1D"))
    )
    (comp (ref "FL8")
      (value "BLM03HG601SZ1D")
      (footprint "eagle-import:R0402")
      (libsource (lib "eagle-import") (part "BLM03HG601SZ1D"))
    )
    (comp (ref "J2")
      (value "XE-1109-001")
      (footprint "eagle-import:XE-1109-001")
      (libsource (lib "eagle-import") (part "XE-1109-001"))
    )
    (comp (ref "R13")
      (value "4k7")
      (footprint "eagle-import:R0402")
      (libsource (lib "eagle-import") (part "RESISTOR0402"))
    )
    (comp (ref "R14")
      (value "4k7")
      (footprint "eagle-import:R0402")
      (libsource (lib "eagle-import") (part "RESISTOR0402"))
    )
    (comp (ref "R15")
      (value "0")
      (footprint "eagle-import:R0402")
      (libsource (lib "eagle-import") (part "RESISTOR0402"))
    )
    (comp (ref "R16")
      (value "10k")
      (footprint "eagle-import:R0402")
      (libsource (lib "eagle-import") (part "RESISTOR0402"))
    )
    (comp (ref "R17")
      (value "2M")
      (footprint "eagle-import:R0402")
      (libsource (lib "eagle-import") (part "RESISTOR0402"))
    )
    (comp (ref "R18")
      (value "2M")
      (footprint "eagle-import:R0402")
      (libsource (lib "eagle-import") (part "RESISTOR0402"))
    )
    (comp (ref "R19")
      (value "1M")
      (footprint "eagle-import:R0402")
      (libsource (lib "eagle-import") (part "RESISTOR0402"))
    )
    (comp (ref "R20")
      (value "100")
      (footprint "eagle-import:R0402")
      (libsource (lib "eagle-import") (part "RESISTOR0402"))
    )
    (comp (ref "R21")
      (value "100")
      (footprint "eagle-import:R0402")
      (libsource (lib "eagle-import") (part "RESISTOR0402"))
    )
    (comp (ref "R22")
      (value "DNP")
      (footprint "eagle-import:R0402")
      (libsource (lib "eagle-import") (part "RESISTOR0402"))
    )
    (comp (ref "R23")
      (value "4k7")
      (footprint "eagle-import:R0402")
      (libsource (lib "eagle-import") (part "RESISTOR0402"))
    )
    (comp (ref "R24")
      (value "4k7")
      (footprint "eagle-import:R0402")
      (libsource (lib "eagle-import") (part "RESISTOR0402"))
    )
    (comp (ref "U4")
      (value "ADUM1250ARZ")
      (footprint "eagle-import:SOIC127P600X175-8N")
      (fields (field (name "MF") "Analog Devices"))
      (libsource (lib "eagle-import") (part "ADUM1250ARZ"))
    )
    (comp (ref "U5")
      (value "MCP9600T-I/MX")
      (footprint "eagle-import:QFN65P500X500X100-21N_MCP9600T-I_MX")
      (fields (field (name "MF") "Microchip Technology"))
      (libsource (lib "eagle-import") (part "MCP9600T-I/MX"))
    )
    (comp (ref "U6")
      (value "ADUM6280")
      (footprint "eagle-import:SOIC127P600X175-8N")
      (libsource (lib "eagle-import") (part "ADUM6280"))
    )
    (comp (ref "C47")
      (value "470p")
      (footprint "eagle-import:C0402")
      (libsource (lib "eagle-import") (part "CAPACITOR0402"))
    )
    (comp (ref "C48")
      (value "100n")
      (footprint "eagle-import:C0402")
      (libsource (lib "eagle-import") (part "CAPACITOR0402"))
    )
    (comp (ref "C49")
      (value "4u7")
      (footprint "eagle-import:C0402")
      (libsource (lib "eagle-import") (part "CAPACITOR0402"))
    )
    (comp (ref "C50")
      (value "4u7")
      (footprint "eagle-import:C0402")
      (libsource (lib "eagle-import") (part "CAPACITOR0402"))
    )
    (comp (ref "C51")
      (value "100n")
      (footprint "eagle-import:C0402")
      (libsource (lib "eagle-import") (part "CAPACITOR0402"))
    )
    (comp (ref "R45")
      (value "WSL2010R5000DEA")
      (footprint "eagle-import:R5025")
      (libsource (lib "eagle-import") (part "R-EU_R5025"))
    )
    (comp (ref "R46")
      (value "22")
      (footprint "eagle-import:R0402")
      (libsource (lib "eagle-import") (part "RESISTOR0402"))
    )
    (comp (ref "R47")
      (value "DNP")
      (footprint "eagle-import:R0402")
      (libsource (lib "eagle-import") (part "RESISTOR0402"))
    )
    (comp (ref "R48")
      (value "DNP")
      (footprint "eagle-import:R0402")
      (libsource (lib "eagle-import") (part "RESISTOR0402"))
    )
    (comp (ref "U14")
      (value "ADC121C027CIMK")
      (footprint "eagle-import:SOT23-6")
      (libsource (lib "eagle-import") (part "ADC121C027CIMK"))
    )
    (comp (ref "U15")
      (value "INA181")
      (footprint "eagle-import:SOT23-6")
      (libsource (lib "eagle-import") (part "INAX81"))
    )
    (comp (ref "C37")
      (value "100n")
      (footprint "eagle-import:C0402")
      (libsource (lib "eagle-import") (part "CAPACITOR0402"))
    )
    (comp (ref "C38")
      (value "100n")
      (footprint "eagle-import:C0402")
      (libsource (lib "eagle-import") (part "CAPACITOR0402"))
    )
    (comp (ref "C39")
      (value "100n")
      (footprint "eagle-import:C0402")
      (libsource (lib "eagle-import") (part "CAPACITOR0402"))
    )
    (comp (ref "C40")
      (value "10u")
      (footprint "eagle-import:C0805")
      (libsource (lib "eagle-import") (part "CAPACITORSMD"))
    )
    (comp (ref "C41")
      (value "100n")
      (footprint "eagle-import:C0402")
      (libsource (lib "eagle-import") (part "CAPACITOR0402"))
    )
    (comp (ref "C42")
      (value "4u7")
      (footprint "eagle-import:C0402")
      (libsource (lib "eagle-import") (part "CAPACITOR0402"))
    )
    (comp (ref "C43")
      (value "100n")
      (footprint "eagle-import:C0402")
      (libsource (lib "eagle-import") (part "CAPACITOR0402"))
    )
    (comp (ref "C44")
      (value "4u7")
      (footprint "eagle-import:C0402")
      (libsource (lib "eagle-import") (part "CAPACITOR0402"))
    )
    (comp (ref "C45")
      (value "10u")
      (footprint "eagle-import:C0805")
      (libsource (lib "eagle-import") (part "CAPACITORSMD"))
    )
    (comp (ref "C46")
      (value "10u")
      (footprint "eagle-import:C0805")
      (libsource (lib "eagle-import") (part "CAPACITORSMD"))
    )
    (comp (ref "FL9")
      (value "BLM03HG601SZ1D")
      (footprint "eagle-import:R0402")
      (libsource (lib "eagle-import") (part "BLM03HG601SZ1D"))
    )
    (comp (ref "FL10")
      (value "BLM03HG601SZ1D")
      (footprint "eagle-import:R0402")
      (libsource (lib "eagle-import") (part "BLM03HG601SZ1D"))
    )
    (comp (ref "R40")
      (value "4k7")
      (footprint "eagle-import:R0402")
      (libsource (lib "eagle-import") (part "RESISTOR0402"))
    )
    (comp (ref "R41")
      (value "4k7")
      (footprint "eagle-import:R0402")
      (libsource (lib "eagle-import") (part "RESISTOR0402"))
    )
    (comp (ref "R42")
      (value "DNP")
      (footprint "eagle-import:R0402")
      (libsource (lib "eagle-import") (part "RESISTOR0402"))
    )
    (comp (ref "R43")
      (value "4k7")
      (footprint "eagle-import:R0402")
      (libsource (lib "eagle-import") (part "RESISTOR0402"))
    )
    (comp (ref "R44")
      (value "4k7")
      (footprint "eagle-import:R0402")
      (libsource (lib "eagle-import") (part "RESISTOR0402"))
    )
    (comp (ref "U12")
      (value "ADUM1250ARZ")
      (footprint "eagle-import:SOIC127P600X175-8N")
      (fields (field (name "MF") "Analog Devices"))
      (libsource (lib "eagle-import") (part "ADUM1250ARZ"))
    )
    (comp (ref "U13")
      (value "ADUM6280")
      (footprint "eagle-import:SOIC127P600X175-8N")
      (libsource (lib "eagle-import") (part "ADUM6280"))
    )
    (comp (ref "D3")
      (value "12V")
      (footprint "eagle-import:SOT23")
      (libsource (lib "eagle-import") (part "ZENERSOT23"))
    )
    (comp (ref "D6")
      (value "DIODE-SOD323-W")
      (footprint "eagle-import:SOD323-W")
      (libsource (lib "eagle-import") (part "DIODE-SOD323-W"))
    )
    (comp (ref "J4")
      (value "SCREW-TERMINAL")
      (footprint "eagle-import:SCREW-TERMINAL-M3")
      (libsource (lib "eagle-import") (part "SCREW-TERMINAL"))
    )
    (comp (ref "J7")
      (value "SCREW-TERMINAL")
      (footprint "eagle-import:SCREW-TERMINAL-M3")
      (libsource (lib "eagle-import") (part "SCREW-TERMINAL"))
    )
    (comp (ref "K1")
      (value "RZ03-1A4-D005")
      (footprint "eagle-import:RELAY_RZ03-1A4-D005")
      (fields (field (name "MF") "TE Connectivity"))
      (libsource (lib "eagle-import") (part "RZ03-1A4-D005"))
    )
    (comp (ref "Q1")
      (value "MOSFET-NSOT23")
      (footprint "eagle-import:SOT23")
      (libsource (lib "eagle-import") (part "MOSFET-NSOT23"))
    )
    (comp (ref "R31")
      (value "10k")
      (footprint "eagle-import:R0805")
      (libsource (lib "eagle-import") (part "RESISTORSMD"))
    )
    (comp (ref "R32")
      (value "10k")
      (footprint "eagle-import:R0805")
      (libsource (lib "eagle-import") (part "RESISTORSMD"))
    )
    (comp (ref "R33")
      (value "180")
      (footprint "eagle-import:R0805")
      (libsource (lib "eagle-import") (part "RESISTORSMD"))
    )
    (comp (ref "U9")
      (value "TLP181(GB,F)")
      (footprint "eagle-import:SOIC254P700X280-4N")
      (fields (field (name "MF") "Toshiba"))
      (libsource (lib "eagle-import") (part "TLP181(GB,F)"))
    )
    (comp (ref "C52")
      (value "470p")
      (footprint "eagle-import:C0402")
      (libsource (lib "eagle-import") (part "CAPACITOR0402"))
    )
    (comp (ref "C53")
      (value "100n")
      (footprint "eagle-import:C0402")
      (libsource (lib "eagle-import") (part "CAPACITOR0402"))
    )
    (comp (ref "C54")
      (value "4u7")
      (footprint "eagle-import:C0402")
      (libsource (lib "eagle-import") (part "CAPACITOR0402"))
    )
    (comp (ref "C55")
      (value "4u7")
      (footprint "eagle-import:C0402")
      (libsource (lib "eagle-import") (part "CAPACITOR0402"))
    )
    (comp (ref "C56")
      (value "100n")
      (footprint "eagle-import:C0402")
      (libsource (lib "eagle-import") (part "CAPACITOR0402"))
    )
    (comp (ref "R49")
      (value "WSL2010R5000DEA")
      (footprint "eagle-import:R5025")
      (libsource (lib "eagle-import") (part "R-EU_R5025"))
    )
    (comp (ref "R50")
      (value "22")
      (footprint "eagle-import:R0402")
      (libsource (lib "eagle-import") (part "RESISTOR0402"))
    )
    (comp (ref "R51")
      (value "DNP")
      (footprint "eagle-import:R0402")
      (libsource (lib "eagle-import") (part "RESISTOR0402"))
    )
    (comp (ref "R52")
      (value "DNP")
      (footprint "eagle-import:R0402")
      (libsource (lib "eagle-import") (part "RESISTOR0402"))
    )
    (comp (ref "U16")
      (value "ADC121C027CIMK")
      (footprint "eagle-import:SOT23-6")
      (libsource (lib "eagle-import") (part "ADC121C027CIMK"))
    )
    (comp (ref "U17")
      (value "INA181")
      (footprint "eagle-import:SOT23-6")
      (libsource (lib "eagle-import") (part "INAX81"))
    )
    (comp (ref "J8")
      (value "2.1MMJACKTHM")
      (footprint "eagle-import:PJ-102A")
      (libsource (lib "eagle-import") (part "2.1MMJACKTHM"))
    )
    (comp (ref "J9")
      (value "NANOFIT")
      (footprint "eagle-import:PINS_4_NANOFIT_RA")
      (libsource (lib "eagle-import") (part "PINS_4-NANOFIT"))
    )
    (comp (ref "P1")
      (value "PINS_1571-0500")
      (footprint "eagle-import:BANNAN_JACK_4MM_H")
      (libsource (lib "eagle-import") (part "PINS_1571-0500"))
    )
    (comp (ref "P2")
      (value "PINS_1571-0500")
      (footprint "eagle-import:BANNAN_JACK_4MM_H")
      (libsource (lib "eagle-import") (part "PINS_1571-0500"))
    )
    (comp (ref "P3")
      (value "PINS_1571-0500")
      (footprint "eagle-import:BANNAN_JACK_4MM_H")
      (libsource (lib "eagle-import") (part "PINS_1571-0500"))
    )
    (comp (ref "P4")
      (value "PINS_1571-0500")
      (footprint "eagle-import:BANNAN_JACK_4MM_H")
      (libsource (lib "eagle-import") (part "PINS_1571-0500"))
    )
    (comp (ref "PCB1")
      (value "MINIPCB_0P100X100")
      (footprint "eagle-import:MINIPCB_DOCK_100X100")
      (fields (field (name "PART_NUMBER") "20A-20"))
      (libsource (lib "eagle-import") (part "MINIPCB_0P100X100"))
    )
    (comp (ref "B3")
      (value "PUSHBUTTON6X6MM")
      (footprint "eagle-import:6X6MM")
      (libsource (lib "eagle-import") (part "PUSHBUTTON6X6MM"))
    )
    (comp (ref "B4")
      (value "PUSHBUTTON6X6MM")
      (footprint "eagle-import:6X6MM")
      (libsource (lib "eagle-import") (part "PUSHBUTTON6X6MM"))
    )
    (comp (ref "C27")
      (value "15p")
      (footprint "eagle-import:C0603")
      (libsource (lib "eagle-import") (part "C0603"))
    )
    (comp (ref "C28")
      (value "15p")
      (footprint "eagle-import:C0603")
      (libsource (lib "eagle-import") (part "C0603"))
    )
    (comp (ref "C29")
      (value "100n")
      (footprint "eagle-import:C0805")
      (libsource (lib "eagle-import") (part "C0805"))
    )
    (comp (ref "C30")
      (value "1u")
      (footprint "eagle-import:C0805")
      (libsource (lib "eagle-import") (part "C-EU_C0805"))
    )
    (comp (ref "C31")
      (value "100p")
      (footprint "eagle-import:C0805")
      (libsource (lib "eagle-import") (part "C-EU_C0805"))
    )
    (comp (ref "C32")
      (value "1u")
      (footprint "eagle-import:C0805")
      (libsource (lib "eagle-import") (part "C0805"))
    )
    (comp (ref "C33")
      (value "10u")
      (footprint "eagle-import:C0805")
      (libsource (lib "eagle-import") (part "C0805"))
    )
    (comp (ref "C34")
      (value "100n")
      (footprint "eagle-import:C0805")
      (libsource (lib "eagle-import") (part "C0805"))
    )
    (comp (ref "C35")
      (value "100n")
      (footprint "eagle-import:C0805")
      (libsource (lib "eagle-import") (part "C0805"))
    )
    (comp (ref "C36")
      (value "1u")
      (footprint "eagle-import:C0805")
      (libsource (lib "eagle-import") (part "C-EU_C0805"))
    )
    (comp (ref "J3")
      (value "ICSP")
      (footprint "eagle-import:PINS_6-2X3_AT")
      (fields
        (field (name "P1") "P1 NAME")
        (field (name "P3") "P3 NAME")
        (field (name "P5") "P5 NAME")
        (field (name "P2") "P2 NAME")
        (field (name "P4") "P4 NAME")
        (field (name "P6") "P6 NAME")
        (field (name "P1_1") "MISO")
        (field (name "P2_1") "VDD")
        (field (name "P3_1") "SCK")
        (field (name "P4_1") "MOSI")
        (field (name "P5_1") "RESET")
        (field (name "P6_1") "GND")
      )
      (libsource (lib "eagle-import") (part "PINS_6-2X3_AT"))
    )
    (comp (ref "LED2")
      (value "LEDSML0805")
      (footprint "eagle-import:SML0805")
      (libsource (lib "eagle-import") (part "LEDSML0805"))
    )
    (comp (ref "R25")
      (value "10k")
      (footprint "eagle-import:R0805")
      (libsource (lib "eagle-import") (part "R-EU__R0805"))
    )
    (comp (ref "R26")
      (value "10R")
      (footprint "eagle-import:R0805")
      (libsource (lib "eagle-import") (part "R-EU__R0805"))
    )
    (comp (ref "R27")
      (value "10k")
      (footprint "eagle-import:R0805")
      (libsource (lib "eagle-import") (part "R-EU__R0805"))
    )
    (comp (ref "R28")
      (value "180")
      (footprint "eagle-import:R0805")
      (libsource (lib "eagle-import") (part "R-EU__R0805"))
    )
    (comp (ref "R29")
      (value "10k")
      (footprint "eagle-import:R0805")
      (libsource (lib "eagle-import") (part "R-EU__R0805"))
    )
    (comp (ref "R30")
      (value "10k")
      (footprint "eagle-import:R0805")
      (libsource (lib "eagle-import") (part "R-EU__R0805"))
    )
    (comp (ref "U7")
      (value "ATMEGA328P-AU")
      (footprint "eagle-import:32A_ATM")
      (fields
        (field (name "MANUFACTURER_PART_NUMBER") "ATMEGA328-AU")
        (field (name "COPYRIGHT") "Copyright (C) 2021 Ultra Librarian. All rights reserved.")
      )
      (libsource (lib "eagle-import") (part "ATMEGA328-AU"))
    )
    (comp (ref "U8")
      (value "VIVA_USB-TTL")
      (footprint "eagle-import:VIVA_USB_TTL_SUBTEXT")
      (libsource (lib "eagle-import") (part "VIVA_USB-TTL"))
    )
    (comp (ref "Y1")
      (value "CRYSTAL-3225_4P")
      (footprint "eagle-import:TXC7M2")
      (libsource (lib "eagle-import") (part "CRYSTAL-3225_4P"))
    )
    (comp (ref "D4")
      (value "12V")
      (footprint "eagle-import:SOT23")
      (libsource (lib "eagle-import") (part "ZENERSOT23"))
    )
    (comp (ref "J5")
      (value "105313-1102")
      (footprint "eagle-import:PINS_2-NANOFIT-H")
      (libsource (lib "eagle-import") (part "PINS_2-NANOFIT-105313-1102"))
    )
    (comp (ref "Q2")
      (value "MOSFET-NDPAK")
      (footprint "eagle-import:DPACK")
      (libsource (lib "eagle-import") (part "MOSFET-NDPAK"))
    )
    (comp (ref "R34")
      (value "10k")
      (footprint "eagle-import:R0805")
      (libsource (lib "eagle-import") (part "RESISTORSMD"))
    )
    (comp (ref "R35")
      (value "10k")
      (footprint "eagle-import:R0805")
      (libsource (lib "eagle-import") (part "RESISTORSMD"))
    )
    (comp (ref "R36")
      (value "180")
      (footprint "eagle-import:R0805")
      (libsource (lib "eagle-import") (part "RESISTORSMD"))
    )
    (comp (ref "U10")
      (value "TLP181(GB,F)")
      (footprint "eagle-import:SOIC254P700X280-4N")
      (fields (field (name "MF") "Toshiba"))
      (libsource (lib "eagle-import") (part "TLP181(GB,F)"))
    )
    (comp (ref "C57")
      (value "4n7")
      (footprint "eagle-import:C0402")
      (libsource (lib "eagle-import") (part "CAPACITOR0402"))
    )
    (comp (ref "C58")
      (value "100n")
      (footprint "eagle-import:C0402")
      (libsource (lib "eagle-import") (part "CAPACITOR0402"))
    )
    (comp (ref "C59")
      (value "4u7")
      (footprint "eagle-import:C0402")
      (libsource (lib "eagle-import") (part "CAPACITOR0402"))
    )
    (comp (ref "R53")
      (value "60")
      (footprint "eagle-import:R0402")
      (libsource (lib "eagle-import") (part "RESISTOR0402"))
    )
    (comp (ref "R54")
      (value "60")
      (footprint "eagle-import:R0402")
      (libsource (lib "eagle-import") (part "RESISTOR0402"))
    )
    (comp (ref "R55")
      (value "300")
      (footprint "eagle-import:R0402")
      (libsource (lib "eagle-import") (part "RESISTOR0402"))
    )
    (comp (ref "U18")
      (value "MCP2561FD-E/MF")
      (footprint "eagle-import:SON65P300X300X100-9N")
      (libsource (lib "eagle-import") (part "MCP2561FD-E/MF"))
    )
  )
  (nets
    (net (code "1") (name "ADC6") (class "Default")
      (node (ref "U7") (pin "19") (pinfunction "ADC6_19") (pintype "passive"))
    )
    (net (code "2") (name "ADC7") (class "Default")
      (node (ref "U7") (pin "22") (pinfunction "ADC7_22") (pintype "passive"))
    )
    (net (code "3") (name "AT-USB-3V3") (class "Default")
      (node (ref "U8") (pin "1.3V3") (pinfunction "(1)3V3_1.3V3") (pintype "bidirectional"))
    )
    (net (code "4") (name "AT-USB-5V") (class "Default")
      (node (ref "U8") (pin "6.5V") (pinfunction "(6)5V_6.5V") (pintype "bidirectional"))
    )
    (net (code "5") (name "AT_MISO") (class "Default")
      (node (ref "J3") (pin "1") (pinfunction "1_1") (pintype "bidirectional"))
      (node (ref "U7") (pin "16") (pinfunction "PB4_16") (pintype "bidirectional"))
    )
    (net (code "6") (name "AT_MOSI") (class "Default")
      (node (ref "J3") (pin "4") (pinfunction "4_4") (pintype "bidirectional"))
      (node (ref "U7") (pin "15") (pinfunction "PB3_15") (pintype "bidirectional"))
    )
    (net (code "7") (name "AT_RST") (class "Default")
      (node (ref "C34") (pin "2") (pinfunction "-_2") (pintype "passive"))
      (node (ref "J3") (pin "5") (pinfunction "5_5") (pintype "bidirectional"))
      (node (ref "R27") (pin "2") (pinfunction "2_2") (pintype "passive"))
      (node (ref "U7") (pin "29") (pinfunction "PC6_29") (pintype "bidirectional"))
    )
    (net (code "8") (name "AT_RXD") (class "Default")
      (node (ref "U7") (pin "30") (pinfunction "PD0_30") (pintype "bidirectional"))
      (node (ref "U8") (pin "4.RDO") (pinfunction "(4)MCU.RX_4.RDO") (pintype "bidirectional"))
    )
    (net (code "9") (name "AT_SCK") (class "Default")
      (node (ref "J3") (pin "3") (pinfunction "3_3") (pintype "bidirectional"))
      (node (ref "R28") (pin "1") (pinfunction "1_1") (pintype "passive"))
      (node (ref "U7") (pin "17") (pinfunction "PB5_17") (pintype "bidirectional"))
    )
    (net (code "10") (name "AT_TXD") (class "Default")
      (node (ref "U7") (pin "31") (pinfunction "PD1_31") (pintype "bidirectional"))
      (node (ref "U8") (pin "3.RXI") (pinfunction "(3)MCU.TX_3.RXI") (pintype "bidirectional"))
    )
    (net (code "11") (name "AVCC") (class "Default")
      (node (ref "C30") (pin "1") (pinfunction "1_1") (pintype "passive"))
      (node (ref "C31") (pin "1") (pinfunction "1_1") (pintype "passive"))
      (node (ref "R26") (pin "2") (pinfunction "2_2") (pintype "passive"))
      (node (ref "U7") (pin "18") (pinfunction "AVCC_18") (pintype "power_in"))
    )
    (net (code "12") (name "CAN-RX") (class "Default")
      (node (ref "U18") (pin "4") (pinfunction "RX_4") (pintype "input"))
    )
    (net (code "13") (name "CAN-STBY") (class "Default")
      (node (ref "U18") (pin "8") (pinfunction "STBY_8") (pintype "power_in"))
    )
    (net (code "14") (name "CAN-TX") (class "Default")
      (node (ref "U18") (pin "1") (pinfunction "TX_1") (pintype "bidirectional"))
    )
    (net (code "15") (name "CANH") (class "Default")
      (node (ref "J9") (pin "3") (pinfunction "3_3") (pintype "bidirectional"))
      (node (ref "R54") (pin "2") (pinfunction "2_2") (pintype "passive"))
      (node (ref "U18") (pin "7") (pinfunction "CANH_7") (pintype "bidirectional"))
    )
    (net (code "16") (name "CANL") (class "Default")
      (node (ref "J9") (pin "2") (pinfunction "2_2") (pintype "bidirectional"))
      (node (ref "R53") (pin "2") (pinfunction "2_2") (pintype "passive"))
      (node (ref "U18") (pin "6") (pinfunction "CANL_6") (pintype "input"))
    )
    (net (code "17") (name "CURRENT-SENSE+") (class "Default")
      (node (ref "Q2") (pin "3") (pinfunction "S_3") (pintype "passive"))
      (node (ref "Q3") (pin "3") (pinfunction "S_3") (pintype "passive"))
      (node (ref "R45") (pin "2") (pinfunction "2_2") (pintype "passive"))
      (node (ref "U15") (pin "3") (pinfunction "3.IN+_3") (pintype "bidirectional"))
    )
    (net (code "18") (name "CURRENT-SENSE-") (class "Default")
      (node (ref "J4") (pin "1") (pinfunction "1_1") (pintype "bidirectional"))
      (node (ref "J4") (pin "2") (pinfunction "1_2") (pintype "bidirectional"))
      (node (ref "J4") (pin "3") (pinfunction "1_3") (pintype "bidirectional"))
      (node (ref "J4") (pin "4") (pinfunction "1_4") (pintype "bidirectional"))
      (node (ref "R45") (pin "1") (pinfunction "1_1") (pintype "passive"))
      (node (ref "U15") (pin "4") (pinfunction "4.IN-_4") (pintype "bidirectional"))
    )
    (net (code "19") (name "DCBUS") (class "Default")
      (node (ref "R33") (pin "1") (pinfunction "1_1") (pintype "passive"))
      (node (ref "U7") (pin "11") (pinfunction "PD7_11") (pintype "bidirectional"))
      (node (ref "U9") (pin "1") (pinfunction "A_1") (pintype "passive"))
    )
    (net (code "20") (name "FAN") (class "Default")
      (node (ref "R39") (pin "1") (pinfunction "1_1") (pintype "passive"))
      (node (ref "U11") (pin "1") (pinfunction "A_1") (pintype "passive"))
      (node (ref "U7") (pin "10") (pinfunction "PD6_10") (pintype "bidirectional"))
    )
    (net (code "21") (name "GND") (class "Default")
      (node (ref "B3") (pin "1.A") (pinfunction "1_1.A") (pintype "bidirectional"))
      (node (ref "B3") (pin "2.A") (pinfunction "1_2.A") (pintype "bidirectional"))
      (node (ref "B4") (pin "1.A") (pinfunction "1_1.A") (pintype "bidirectional"))
      (node (ref "B4") (pin "2.A") (pinfunction "1_2.A") (pintype "bidirectional"))
      (node (ref "C10") (pin "2") (pinfunction "-_2") (pintype "passive"))
      (node (ref "C11") (pin "2ASDF") (pinfunction "-_2ASDF") (pintype "passive"))
      (node (ref "C12") (pin "2") (pinfunction "-_2") (pintype "passive"))
      (node (ref "C13") (pin "2ASDF") (pinfunction "-_2ASDF") (pintype "passive"))
      (node (ref "C18") (pin "2") (pinfunction "-_2") (pintype "passive"))
      (node (ref "C19") (pin "2ASDF") (pinfunction "-_2ASDF") (pintype "passive"))
      (node (ref "C22") (pin "2") (pinfunction "-_2") (pintype "passive"))
      (node (ref "C23") (pin "2") (pinfunction "-_2") (pintype "passive"))
      (node (ref "C25") (pin "2ASDF") (pinfunction "-_2ASDF") (pintype "passive"))
      (node (ref "C27") (pin "1") (pinfunction "-_1") (pintype "passive"))
      (node (ref "C28") (pin "1") (pinfunction "-_1") (pintype "passive"))
      (node (ref "C29") (pin "2") (pinfunction "-_2") (pintype "passive"))
      (node (ref "C30") (pin "2") (pinfunction "2_2") (pintype "passive"))
      (node (ref "C31") (pin "2") (pinfunction "2_2") (pintype "passive"))
      (node (ref "C32") (pin "2") (pinfunction "-_2") (pintype "passive"))
      (node (ref "C33") (pin "2") (pinfunction "-_2") (pintype "passive"))
      (node (ref "C35") (pin "2") (pinfunction "-_2") (pintype "passive"))
      (node (ref "C36") (pin "2") (pinfunction "2_2") (pintype "passive"))
      (node (ref "C39") (pin "2") (pinfunction "-_2") (pintype "passive"))
      (node (ref "C40") (pin "2ASDF") (pinfunction "-_2ASDF") (pintype "passive"))
      (node (ref "C43") (pin "2") (pinfunction "-_2") (pintype "passive"))
      (node (ref "C44") (pin "2") (pinfunction "-_2") (pintype "passive"))
      (node (ref "C46") (pin "2ASDF") (pinfunction "-_2ASDF") (pintype "passive"))
      (node (ref "C52") (pin "2") (pinfunction "-_2") (pintype "passive"))
      (node (ref "C53") (pin "2") (pinfunction "-_2") (pintype "passive"))
      (node (ref "C54") (pin "2") (pinfunction "-_2") (pintype "passive"))
      (node (ref "C55") (pin "2") (pinfunction "-_2") (pintype "passive"))
      (node (ref "C56") (pin "2") (pinfunction "-_2") (pintype "passive"))
      (node (ref "C57") (pin "2") (pinfunction "-_2") (pintype "passive"))
      (node (ref "C58") (pin "2") (pinfunction "-_2") (pintype "passive"))
      (node (ref "C59") (pin "2") (pinfunction "-_2") (pintype "passive"))
      (node (ref "C9") (pin "2") (pinfunction "-_2") (pintype "passive"))
      (node (ref "J3") (pin "6") (pinfunction "6_6") (pintype "bidirectional"))
      (node (ref "J8") (pin "RING") (pinfunction "RING_RING") (pintype "bidirectional"))
      (node (ref "J9") (pin "1") (pinfunction "1_1") (pintype "bidirectional"))
      (node (ref "LED2") (pin "C") (pinfunction "C_C") (pintype "passive"))
      (node (ref "R52") (pin "2") (pinfunction "2_2") (pintype "passive"))
      (node (ref "U10") (pin "3") (pinfunction "C_3") (pintype "passive"))
      (node (ref "U11") (pin "3") (pinfunction "C_3") (pintype "passive"))
      (node (ref "U12") (pin "4") (pinfunction "GND1_4") (pintype "passive"))
      (node (ref "U13") (pin "2") (pinfunction "GND1_2") (pintype "passive"))
      (node (ref "U13") (pin "4") (pinfunction "GND1_4") (pintype "passive"))
      (node (ref "U16") (pin "2") (pinfunction "2.GND_2") (pintype "bidirectional"))
      (node (ref "U17") (pin "2") (pinfunction "2.GND_2") (pintype "bidirectional"))
      (node (ref "U17") (pin "5") (pinfunction "5.REF_5") (pintype "bidirectional"))
      (node (ref "U18") (pin "2") (pinfunction "VSS_2") (pintype "passive"))
      (node (ref "U18") (pin "9") (pinfunction "VSS_9") (pintype "passive"))
      (node (ref "U2") (pin "4") (pinfunction "GND1_4") (pintype "passive"))
      (node (ref "U3") (pin "2") (pinfunction "GND1_2") (pintype "passive"))
      (node (ref "U3") (pin "4") (pinfunction "GND1_4") (pintype "passive"))
      (node (ref "U4") (pin "4") (pinfunction "GND1_4") (pintype "passive"))
      (node (ref "U6") (pin "2") (pinfunction "GND1_2") (pintype "passive"))
      (node (ref "U6") (pin "4") (pinfunction "GND1_4") (pintype "passive"))
      (node (ref "U7") (pin "21") (pinfunction "GND_21") (pintype "power_in"))
      (node (ref "U7") (pin "3") (pinfunction "GND_2_3") (pintype "power_in"))
      (node (ref "U7") (pin "5") (pinfunction "GND_3_5") (pintype "power_in"))
      (node (ref "U8") (pin "5.GND") (pinfunction "(5)GND_5.GND") (pintype "bidirectional"))
      (node (ref "U9") (pin "3") (pinfunction "C_3") (pintype "passive"))
    )
    (net (code "22") (name "GNDA") (class "Default")
      (node (ref "C14") (pin "1") (pinfunction "+_1") (pintype "passive"))
      (node (ref "C15") (pin "1") (pinfunction "+_1") (pintype "passive"))
      (node (ref "C17") (pin "2") (pinfunction "-_2") (pintype "passive"))
      (node (ref "C2") (pin "1") (pinfunction "+_1") (pintype "passive"))
      (node (ref "C20") (pin "2") (pinfunction "-_2") (pintype "passive"))
      (node (ref "C21") (pin "2") (pinfunction "-_2") (pintype "passive"))
      (node (ref "C24") (pin "2ASDF") (pinfunction "-_2ASDF") (pintype "passive"))
      (node (ref "C3") (pin "1") (pinfunction "+_1") (pintype "passive"))
      (node (ref "C4") (pin "2") (pinfunction "-_2") (pintype "passive"))
      (node (ref "C5") (pin "2") (pinfunction "-_2") (pintype "passive"))
      (node (ref "C6") (pin "2ASDF") (pinfunction "-_2ASDF") (pintype "passive"))
      (node (ref "C7") (pin "2") (pinfunction "-_2") (pintype "passive"))
      (node (ref "D1") (pin "1") (pinfunction "A1_1") (pintype "bidirectional"))
      (node (ref "D1") (pin "4") (pinfunction "A1_4") (pintype "bidirectional"))
      (node (ref "D2") (pin "1") (pinfunction "A1_1") (pintype "bidirectional"))
      (node (ref "D2") (pin "4") (pinfunction "A1_4") (pintype "bidirectional"))
      (node (ref "FL4") (pin "1") (pinfunction "1_1") (pintype "passive"))
      (node (ref "FL7") (pin "1") (pinfunction "1_1") (pintype "passive"))
      (node (ref "R1") (pin "1") (pinfunction "1_1") (pintype "passive"))
      (node (ref "R11") (pin "1") (pinfunction "1_1") (pintype "passive"))
      (node (ref "R15") (pin "1") (pinfunction "1_1") (pintype "passive"))
      (node (ref "R17") (pin "1") (pinfunction "1_1") (pintype "passive"))
      (node (ref "R18") (pin "1") (pinfunction "1_1") (pintype "passive"))
      (node (ref "R2") (pin "1") (pinfunction "1_1") (pintype "passive"))
      (node (ref "R22") (pin "1") (pinfunction "1_1") (pintype "passive"))
      (node (ref "R6") (pin "1") (pinfunction "1_1") (pintype "passive"))
      (node (ref "U1") (pin "1") (pinfunction "GND_1") (pintype "power_in"))
      (node (ref "U1") (pin "10") (pinfunction "GND_10") (pintype "power_in"))
      (node (ref "U1") (pin "13") (pinfunction "GND_13") (pintype "power_in"))
      (node (ref "U1") (pin "17") (pinfunction "GND_17") (pintype "power_in"))
      (node (ref "U1") (pin "18") (pinfunction "GND_18") (pintype "power_in"))
      (node (ref "U1") (pin "21") (pinfunction "EXP_21") (pintype "power_in"))
      (node (ref "U1") (pin "22") (pinfunction "EXP_22") (pintype "power_in"))
      (node (ref "U1") (pin "23") (pinfunction "EXP_23") (pintype "power_in"))
      (node (ref "U1") (pin "24") (pinfunction "EXP_24") (pintype "power_in"))
      (node (ref "U1") (pin "25") (pinfunction "EXP_25") (pintype "power_in"))
      (node (ref "U1") (pin "26") (pinfunction "EXP_26") (pintype "power_in"))
      (node (ref "U1") (pin "27") (pinfunction "EXP_27") (pintype "power_in"))
      (node (ref "U1") (pin "28") (pinfunction "EXP_28") (pintype "power_in"))
      (node (ref "U1") (pin "29") (pinfunction "EXP_29") (pintype "power_in"))
      (node (ref "U1") (pin "3") (pinfunction "GND_3") (pintype "power_in"))
      (node (ref "U1") (pin "30") (pinfunction "EXP_30") (pintype "power_in"))
      (node (ref "U1") (pin "5") (pinfunction "GND_5") (pintype "power_in"))
      (node (ref "U1") (pin "6") (pinfunction "GND_6") (pintype "power_in"))
      (node (ref "U1") (pin "7") (pinfunction "GND_7") (pintype "power_in"))
      (node (ref "U1") (pin "9") (pinfunction "GND_9") (pintype "power_in"))
      (node (ref "U2") (pin "5") (pinfunction "GND2_5") (pintype "passive"))
      (node (ref "U4") (pin "5") (pinfunction "GND2_5") (pintype "passive"))
      (node (ref "U5") (pin "1") (pinfunction "GND_1") (pintype "power_in"))
      (node (ref "U5") (pin "10") (pinfunction "GND_10") (pintype "power_in"))
      (node (ref "U5") (pin "13") (pinfunction "GND_13") (pintype "power_in"))
      (node (ref "U5") (pin "17") (pinfunction "GND_17") (pintype "power_in"))
      (node (ref "U5") (pin "18") (pinfunction "GND_18") (pintype "power_in"))
      (node (ref "U5") (pin "21") (pinfunction "EXP_21") (pintype "power_in"))
      (node (ref "U5") (pin "22") (pinfunction "EXP_22") (pintype "power_in"))
      (node (ref "U5") (pin "23") (pinfunction "EXP_23") (pintype "power_in"))
      (node (ref "U5") (pin "24") (pinfunction "EXP_24") (pintype "power_in"))
      (node (ref "U5") (pin "25") (pinfunction "EXP_25") (pintype "power_in"))
      (node (ref "U5") (pin "26") (pinfunction "EXP_26") (pintype "power_in"))
      (node (ref "U5") (pin "27") (pinfunction "EXP_27") (pintype "power_in"))
      (node (ref "U5") (pin "28") (pinfunction "EXP_28") (pintype "power_in"))
      (node (ref "U5") (pin "29") (pinfunction "EXP_29") (pintype "power_in"))
      (node (ref "U5") (pin "3") (pinfunction "GND_3") (pintype "power_in"))
      (node (ref "U5") (pin "30") (pinfunction "EXP_30") (pintype "power_in"))
      (node (ref "U5") (pin "5") (pinfunction "GND_5") (pintype "power_in"))
      (node (ref "U5") (pin "6") (pinfunction "GND_6") (pintype "power_in"))
      (node (ref "U5") (pin "7") (pinfunction "GND_7") (pintype "power_in"))
      (node (ref "U5") (pin "9") (pinfunction "GND_9") (pintype "power_in"))
    )
    (net (code "23") (name "GNDB") (class "Default")
      (node (ref "C38") (pin "2") (pinfunction "-_2") (pintype "passive"))
      (node (ref "C41") (pin "2") (pinfunction "-_2") (pintype "passive"))
      (node (ref "C42") (pin "2") (pinfunction "-_2") (pintype "passive"))
      (node (ref "C45") (pin "2ASDF") (pinfunction "-_2ASDF") (pintype "passive"))
      (node (ref "C47") (pin "2") (pinfunction "-_2") (pintype "passive"))
      (node (ref "C48") (pin "2") (pinfunction "-_2") (pintype "passive"))
      (node (ref "C49") (pin "2") (pinfunction "-_2") (pintype "passive"))
      (node (ref "C50") (pin "2") (pinfunction "-_2") (pintype "passive"))
      (node (ref "C51") (pin "2") (pinfunction "-_2") (pintype "passive"))
      (node (ref "D3") (pin "1") (pinfunction "A_1") (pintype "passive"))
      (node (ref "D4") (pin "1") (pinfunction "A_1") (pintype "passive"))
      (node (ref "D5") (pin "1") (pinfunction "A_1") (pintype "passive"))
      (node (ref "FL9") (pin "1") (pinfunction "1_1") (pintype "passive"))
      (node (ref "Q1") (pin "2") (pinfunction "S_2") (pintype "passive"))
      (node (ref "R32") (pin "1") (pinfunction "1_1") (pintype "passive"))
      (node (ref "R35") (pin "1") (pinfunction "1_1") (pintype "passive"))
      (node (ref "R38") (pin "1") (pinfunction "1_1") (pintype "passive"))
      (node (ref "R42") (pin "1") (pinfunction "1_1") (pintype "passive"))
      (node (ref "R48") (pin "2") (pinfunction "2_2") (pintype "passive"))
      (node (ref "U14") (pin "2") (pinfunction "2.GND_2") (pintype "bidirectional"))
      (node (ref "U15") (pin "2") (pinfunction "2.GND_2") (pintype "bidirectional"))
      (node (ref "U15") (pin "5") (pinfunction "5.REF_5") (pintype "bidirectional"))
    )
    (net (code "24") (name "HEATER") (class "Default")
      (node (ref "R36") (pin "1") (pinfunction "1_1") (pintype "passive"))
      (node (ref "U10") (pin "1") (pinfunction "A_1") (pintype "passive"))
      (node (ref "U7") (pin "9") (pinfunction "PD5_9") (pintype "bidirectional"))
    )
    (net (code "25") (name "ISO-SCL") (class "Default")
      (node (ref "R41") (pin "1") (pinfunction "1_1") (pintype "passive"))
      (node (ref "U12") (pin "6") (pinfunction "SCL2_6") (pintype "input"))
      (node (ref "U14") (pin "5") (pinfunction "5.SCL_5") (pintype "bidirectional"))
    )
    (net (code "26") (name "ISO-SDA") (class "Default")
      (node (ref "R40") (pin "1") (pinfunction "1_1") (pintype "passive"))
      (node (ref "U12") (pin "7") (pinfunction "SDA2_7") (pintype "bidirectional"))
      (node (ref "U14") (pin "6") (pinfunction "6.SDA_6") (pintype "bidirectional"))
    )
    (net (code "27") (name "LEAKAGE-CURRENT+") (class "Default")
      (node (ref "P4") (pin "1") (pinfunction "1_1") (pintype "bidirectional"))
      (node (ref "P4") (pin "2") (pinfunction "1_2") (pintype "bidirectional"))
      (node (ref "R49") (pin "2") (pinfunction "2_2") (pintype "passive"))
      (node (ref "U17") (pin "3") (pinfunction "3.IN+_3") (pintype "bidirectional"))
    )
    (net (code "28") (name "LEAKAGE-CURRENT-") (class "Default")
      (node (ref "P3") (pin "1") (pinfunction "1_1") (pintype "bidirectional"))
      (node (ref "P3") (pin "2") (pinfunction "1_2") (pintype "bidirectional"))
      (node (ref "R49") (pin "1") (pinfunction "1_1") (pintype "passive"))
      (node (ref "U17") (pin "4") (pinfunction "4.IN-_4") (pintype "bidirectional"))
    )
    (net (code "29") (name "Net-(C1-+)") (class "Default")
      (node (ref "C1") (pin "1") (pinfunction "+_1") (pintype "passive"))
      (node (ref "R3") (pin "2") (pinfunction "2_2") (pintype "passive"))
      (node (ref "U1") (pin "2") (pinfunction "VIN+_2") (pintype "input"))
    )
    (net (code "30") (name "Net-(C1--)") (class "Default")
      (node (ref "C1") (pin "2") (pinfunction "-_2") (pintype "passive"))
      (node (ref "R4") (pin "2") (pinfunction "2_2") (pintype "passive"))
      (node (ref "U1") (pin "4") (pinfunction "VIN-_4") (pintype "input"))
    )
    (net (code "31") (name "Net-(C2--)") (class "Default")
      (node (ref "C2") (pin "2") (pinfunction "-_2") (pintype "passive"))
      (node (ref "C3") (pin "2") (pinfunction "-_2") (pintype "passive"))
      (node (ref "C4") (pin "1") (pinfunction "+_1") (pintype "passive"))
      (node (ref "C5") (pin "1") (pinfunction "+_1") (pintype "passive"))
      (node (ref "C6") (pin "1ASD") (pinfunction "+_1ASD") (pintype "passive"))
      (node (ref "C7") (pin "1") (pinfunction "+_1") (pintype "passive"))
      (node (ref "D1") (pin "2") (pinfunction "C2_2") (pintype "bidirectional"))
      (node (ref "D1") (pin "5") (pinfunction "C2_5") (pintype "bidirectional"))
      (node (ref "FL3") (pin "1") (pinfunction "1_1") (pintype "passive"))
      (node (ref "R10") (pin "2") (pinfunction "2_2") (pintype "passive"))
      (node (ref "R5") (pin "2") (pinfunction "2_2") (pintype "passive"))
      (node (ref "R7") (pin "2") (pinfunction "2_2") (pintype "passive"))
      (node (ref "R8") (pin "2") (pinfunction "2_2") (pintype "passive"))
      (node (ref "R9") (pin "2") (pinfunction "2_2") (pintype "passive"))
      (node (ref "U1") (pin "8") (pinfunction "VDD_8") (pintype "power_in"))
      (node (ref "U2") (pin "8") (pinfunction "VDD2_8") (pintype "power_in"))
    )
    (net (code "32") (name "Net-(C8-+)") (class "Default")
      (node (ref "C8") (pin "1") (pinfunction "+_1") (pintype "passive"))
      (node (ref "FL3") (pin "2") (pinfunction "2_2") (pintype "passive"))
      (node (ref "U3") (pin "6") (pinfunction "VISO_6") (pintype "power_in"))
    )
    (net (code "33") (name "Net-(C8--)") (class "Default")
      (node (ref "C8") (pin "2") (pinfunction "-_2") (pintype "passive"))
      (node (ref "FL4") (pin "2") (pinfunction "2_2") (pintype "passive"))
      (node (ref "U3") (pin "5") (pinfunction "GNDISO_5") (pintype "passive"))
      (node (ref "U3") (pin "7") (pinfunction "GNDISO_7") (pintype "passive"))
    )
    (net (code "34") (name "Net-(C14--)") (class "Default")
      (node (ref "C14") (pin "2") (pinfunction "-_2") (pintype "passive"))
      (node (ref "C15") (pin "2") (pinfunction "-_2") (pintype "passive"))
      (node (ref "C17") (pin "1") (pinfunction "+_1") (pintype "passive"))
      (node (ref "C20") (pin "1") (pinfunction "+_1") (pintype "passive"))
      (node (ref "C21") (pin "1") (pinfunction "+_1") (pintype "passive"))
      (node (ref "C24") (pin "1ASD") (pinfunction "+_1ASD") (pintype "passive"))
      (node (ref "D2") (pin "2") (pinfunction "C2_2") (pintype "bidirectional"))
      (node (ref "D2") (pin "5") (pinfunction "C2_5") (pintype "bidirectional"))
      (node (ref "FL8") (pin "1") (pinfunction "1_1") (pintype "passive"))
      (node (ref "R13") (pin "2") (pinfunction "2_2") (pintype "passive"))
      (node (ref "R14") (pin "2") (pinfunction "2_2") (pintype "passive"))
      (node (ref "R16") (pin "2") (pinfunction "2_2") (pintype "passive"))
      (node (ref "R19") (pin "2") (pinfunction "2_2") (pintype "passive"))
      (node (ref "R23") (pin "2") (pinfunction "2_2") (pintype "passive"))
      (node (ref "U4") (pin "8") (pinfunction "VDD2_8") (pintype "power_in"))
      (node (ref "U5") (pin "8") (pinfunction "VDD_8") (pintype "power_in"))
    )
    (net (code "35") (name "Net-(C16-+)") (class "Default")
      (node (ref "C16") (pin "1") (pinfunction "+_1") (pintype "passive"))
      (node (ref "FL8") (pin "2") (pinfunction "2_2") (pintype "passive"))
      (node (ref "U6") (pin "6") (pinfunction "VISO_6") (pintype "power_in"))
    )
    (net (code "36") (name "Net-(C16--)") (class "Default")
      (node (ref "C16") (pin "2") (pinfunction "-_2") (pintype "passive"))
      (node (ref "FL7") (pin "2") (pinfunction "2_2") (pintype "passive"))
      (node (ref "U6") (pin "5") (pinfunction "GNDISO_5") (pintype "passive"))
      (node (ref "U6") (pin "7") (pinfunction "GNDISO_7") (pintype "passive"))
    )
    (net (code "37") (name "Net-(C26-+)") (class "Default")
      (node (ref "C26") (pin "1") (pinfunction "+_1") (pintype "passive"))
      (node (ref "R20") (pin "2") (pinfunction "2_2") (pintype "passive"))
      (node (ref "U5") (pin "2") (pinfunction "VIN+_2") (pintype "input"))
    )
    (net (code "38") (name "Net-(C26--)") (class "Default")
      (node (ref "C26") (pin "2") (pinfunction "-_2") (pintype "passive"))
      (node (ref "R21") (pin "2") (pinfunction "2_2") (pintype "passive"))
      (node (ref "U5") (pin "4") (pinfunction "VIN-_4") (pintype "input"))
    )
    (net (code "39") (name "Net-(C29-+)") (class "Default")
      (node (ref "B4") (pin "3.B") (pinfunction "2_3.B") (pintype "bidirectional"))
      (node (ref "B4") (pin "4.B") (pinfunction "2_4.B") (pintype "bidirectional"))
      (node (ref "C29") (pin "1") (pinfunction "+_1") (pintype "passive"))
      (node (ref "R25") (pin "2") (pinfunction "2_2") (pintype "passive"))
      (node (ref "R27") (pin "1") (pinfunction "1_1") (pintype "passive"))
    )
    (net (code "40") (name "Net-(C34-+)") (class "Default")
      (node (ref "C34") (pin "1") (pinfunction "+_1") (pintype "passive"))
      (node (ref "U8") (pin "2.DTR") (pinfunction "(2)DTR_2.DTR") (pintype "bidirectional"))
    )
    (net (code "41") (name "Net-(C35-+)") (class "Default")
      (node (ref "B3") (pin "3.B") (pinfunction "2_3.B") (pintype "bidirectional"))
      (node (ref "B3") (pin "4.B") (pinfunction "2_4.B") (pintype "bidirectional"))
      (node (ref "C35") (pin "1") (pinfunction "+_1") (pintype "passive"))
      (node (ref "R29") (pin "2") (pinfunction "2_2") (pintype "passive"))
      (node (ref "R30") (pin "2") (pinfunction "2_2") (pintype "passive"))
    )
    (net (code "42") (name "Net-(C37-+)") (class "Default")
      (node (ref "C37") (pin "1") (pinfunction "+_1") (pintype "passive"))
      (node (ref "FL10") (pin "2") (pinfunction "2_2") (pintype "passive"))
      (node (ref "U13") (pin "6") (pinfunction "VISO_6") (pintype "power_in"))
    )
    (net (code "43") (name "Net-(C37--)") (class "Default")
      (node (ref "C37") (pin "2") (pinfunction "-_2") (pintype "passive"))
      (node (ref "FL9") (pin "2") (pinfunction "2_2") (pintype "passive"))
      (node (ref "U13") (pin "5") (pinfunction "GNDISO_5") (pintype "passive"))
      (node (ref "U13") (pin "7") (pinfunction "GNDISO_7") (pintype "passive"))
    )
    (net (code "44") (name "Net-(C47-+)") (class "Default")
      (node (ref "C47") (pin "1") (pinfunction "+_1") (pintype "passive"))
      (node (ref "R46") (pin "2") (pinfunction "2_2") (pintype "passive"))
      (node (ref "U14") (pin "3") (pinfunction "3.VIN_3") (pintype "bidirectional"))
    )
    (net (code "45") (name "Net-(C52-+)") (class "Default")
      (node (ref "C52") (pin "1") (pinfunction "+_1") (pintype "passive"))
      (node (ref "R50") (pin "2") (pinfunction "2_2") (pintype "passive"))
      (node (ref "U16") (pin "3") (pinfunction "3.VIN_3") (pintype "bidirectional"))
    )
    (net (code "46") (name "Net-(C57-+)") (class "Default")
      (node (ref "C57") (pin "1") (pinfunction "+_1") (pintype "passive"))
      (node (ref "R53") (pin "1") (pinfunction "1_1") (pintype "passive"))
      (node (ref "R54") (pin "1") (pinfunction "1_1") (pintype "passive"))
      (node (ref "R55") (pin "2") (pinfunction "2_2") (pintype "passive"))
    )
    (net (code "47") (name "Net-(D1A-COM)") (class "Default")
      (node (ref "D1") (pin "6") (pinfunction "COM_6") (pintype "bidirectional"))
      (node (ref "FL1") (pin "2") (pinfunction "2_2") (pintype "passive"))
      (node (ref "R1") (pin "2") (pinfunction "2_2") (pintype "passive"))
      (node (ref "R3") (pin "1") (pinfunction "1_1") (pintype "passive"))
      (node (ref "R5") (pin "1") (pinfunction "1_1") (pintype "passive"))
    )
    (net (code "48") (name "Net-(D1B-COM)") (class "Default")
      (node (ref "D1") (pin "3") (pinfunction "COM_3") (pintype "bidirectional"))
      (node (ref "FL2") (pin "2") (pinfunction "2_2") (pintype "passive"))
      (node (ref "R2") (pin "2") (pinfunction "2_2") (pintype "passive"))
      (node (ref "R4") (pin "1") (pinfunction "1_1") (pintype "passive"))
    )
    (net (code "49") (name "Net-(D2A-COM)") (class "Default")
      (node (ref "D2") (pin "6") (pinfunction "COM_6") (pintype "bidirectional"))
      (node (ref "FL6") (pin "2") (pinfunction "2_2") (pintype "passive"))
      (node (ref "R18") (pin "2") (pinfunction "2_2") (pintype "passive"))
      (node (ref "R19") (pin "1") (pinfunction "1_1") (pintype "passive"))
      (node (ref "R20") (pin "1") (pinfunction "1_1") (pintype "passive"))
    )
    (net (code "50") (name "Net-(D2B-COM)") (class "Default")
      (node (ref "D2") (pin "3") (pinfunction "COM_3") (pintype "bidirectional"))
      (node (ref "FL5") (pin "2") (pinfunction "2_2") (pintype "passive"))
      (node (ref "R17") (pin "2") (pinfunction "2_2") (pintype "passive"))
      (node (ref "R21") (pin "1") (pinfunction "1_1") (pintype "passive"))
    )
    (net (code "51") (name "Net-(D3-C)") (class "Default")
      (node (ref "D3") (pin "3") (pinfunction "C_3") (pintype "passive"))
      (node (ref "Q1") (pin "1") (pinfunction "G_1") (pintype "passive"))
      (node (ref "R32") (pin "2") (pinfunction "2_2") (pintype "passive"))
      (node (ref "U9") (pin "4") (pinfunction "ET_4") (pintype "passive"))
    )
    (net (code "52") (name "Net-(D4-C)") (class "Default")
      (node (ref "D4") (pin "3") (pinfunction "C_3") (pintype "passive"))
      (node (ref "Q2") (pin "1") (pinfunction "G_1") (pintype "passive"))
      (node (ref "R35") (pin "2") (pinfunction "2_2") (pintype "passive"))
      (node (ref "U10") (pin "4") (pinfunction "ET_4") (pintype "passive"))
    )
    (net (code "53") (name "Net-(D5-C)") (class "Default")
      (node (ref "D5") (pin "3") (pinfunction "C_3") (pintype "passive"))
      (node (ref "Q3") (pin "1") (pinfunction "G_1") (pintype "passive"))
      (node (ref "R38") (pin "2") (pinfunction "2_2") (pintype "passive"))
      (node (ref "U11") (pin "4") (pinfunction "ET_4") (pintype "passive"))
    )
    (net (code "54") (name "Net-(D6-PadC)") (class "Default")
      (node (ref "D6") (pin "C") (pinfunction "C_C") (pintype "passive"))
      (node (ref "J7") (pin "1") (pinfunction "1_1") (pintype "bidirectional"))
      (node (ref "J7") (pin "2") (pinfunction "1_2") (pintype "bidirectional"))
      (node (ref "J7") (pin "3") (pinfunction "1_3") (pintype "bidirectional"))
      (node (ref "J7") (pin "4") (pinfunction "1_4") (pintype "bidirectional"))
      (node (ref "K1") (pin "11.1") (pinfunction "11_11.1") (pintype "passive"))
      (node (ref "K1") (pin "11.2") (pinfunction "11_11.2") (pintype "passive"))
      (node (ref "K1") (pin "A2") (pinfunction "A2_A2") (pintype "passive"))
      (node (ref "R31") (pin "2") (pinfunction "2_2") (pintype "passive"))
    )
    (net (code "55") (name "Net-(FL1-Pad1)") (class "Default")
      (node (ref "FL1") (pin "1") (pinfunction "1_1") (pintype "passive"))
      (node (ref "J1") (pin "2") (pinfunction "2_2") (pintype "bidirectional"))
    )
    (net (code "56") (name "Net-(FL2-Pad1)") (class "Default")
      (node (ref "FL2") (pin "1") (pinfunction "1_1") (pintype "passive"))
      (node (ref "J1") (pin "1") (pinfunction "1_1") (pintype "bidirectional"))
    )
    (net (code "57") (name "Net-(FL5-Pad1)") (class "Default")
      (node (ref "FL5") (pin "1") (pinfunction "1_1") (pintype "passive"))
      (node (ref "J2") (pin "1") (pinfunction "1_1") (pintype "bidirectional"))
    )
    (net (code "58") (name "Net-(FL6-Pad1)") (class "Default")
      (node (ref "FL6") (pin "1") (pinfunction "1_1") (pintype "passive"))
      (node (ref "J2") (pin "2") (pinfunction "2_2") (pintype "bidirectional"))
    )
    (net (code "59") (name "Net-(LED2-PadA)") (class "Default")
      (node (ref "LED2") (pin "A") (pinfunction "A_A") (pintype "passive"))
      (node (ref "R28") (pin "2") (pinfunction "2_2") (pintype "passive"))
    )
    (net (code "60") (name "Net-(P1-1-Pad2)") (class "Default")
      (node (ref "P1") (pin "1") (pinfunction "1_1") (pintype "bidirectional"))
      (node (ref "P1") (pin "2") (pinfunction "1_2") (pintype "bidirectional"))
      (node (ref "P2") (pin "1") (pinfunction "1_1") (pintype "bidirectional"))
      (node (ref "P2") (pin "2") (pinfunction "1_2") (pintype "bidirectional"))
    )
    (net (code "61") (name "Net-(Q1-D)") (class "Default")
      (node (ref "D6") (pin "A") (pinfunction "A_A") (pintype "passive"))
      (node (ref "K1") (pin "A1") (pinfunction "A1_A1") (pintype "passive"))
      (node (ref "Q1") (pin "3") (pinfunction "D_3") (pintype "passive"))
    )
    (net (code "62") (name "Net-(Q2-D)") (class "Default")
      (node (ref "J5") (pin "2") (pinfunction "2_2") (pintype "bidirectional"))
      (node (ref "Q2") (pin "4") (pinfunction "D_4") (pintype "passive"))
    )
    (net (code "63") (name "Net-(Q3-D)") (class "Default")
      (node (ref "J6") (pin "2") (pinfunction "2_2") (pintype "bidirectional"))
      (node (ref "Q3") (pin "4") (pinfunction "D_4") (pintype "passive"))
    )
    (net (code "64") (name "Net-(U1-ADDR)") (class "Default")
      (node (ref "R6") (pin "2") (pinfunction "2_2") (pintype "passive"))
      (node (ref "R7") (pin "1") (pinfunction "1_1") (pintype "passive"))
      (node (ref "U1") (pin "16") (pinfunction "ADDR_16") (pintype "input"))
    )
    (net (code "65") (name "Net-(U1-SCL)") (class "Default")
      (node (ref "R9") (pin "1") (pinfunction "1_1") (pintype "passive"))
      (node (ref "U1") (pin "19") (pinfunction "SCL_19") (pintype "input"))
      (node (ref "U2") (pin "6") (pinfunction "SCL2_6") (pintype "input"))
    )
    (net (code "66") (name "Net-(U1-SDA)") (class "Default")
      (node (ref "R8") (pin "1") (pinfunction "1_1") (pintype "passive"))
      (node (ref "U1") (pin "20") (pinfunction "SDA_20") (pintype "bidirectional"))
      (node (ref "U2") (pin "7") (pinfunction "SDA2_7") (pintype "bidirectional"))
    )
    (net (code "67") (name "Net-(U3-VSEL)") (class "Default")
      (node (ref "R10") (pin "1") (pinfunction "1_1") (pintype "passive"))
      (node (ref "R11") (pin "2") (pinfunction "2_2") (pintype "passive"))
      (node (ref "U3") (pin "8") (pinfunction "VSEL_8") (pintype "power_in"))
    )
    (net (code "68") (name "Net-(U4-SCL2)") (class "Default")
      (node (ref "R14") (pin "1") (pinfunction "1_1") (pintype "passive"))
      (node (ref "U4") (pin "6") (pinfunction "SCL2_6") (pintype "input"))
      (node (ref "U5") (pin "19") (pinfunction "SCL_19") (pintype "input"))
    )
    (net (code "69") (name "Net-(U4-SDA2)") (class "Default")
      (node (ref "R13") (pin "1") (pinfunction "1_1") (pintype "passive"))
      (node (ref "U4") (pin "7") (pinfunction "SDA2_7") (pintype "bidirectional"))
      (node (ref "U5") (pin "20") (pinfunction "SDA_20") (pintype "bidirectional"))
    )
    (net (code "70") (name "Net-(U5-ADDR)") (class "Default")
      (node (ref "R15") (pin "2") (pinfunction "2_2") (pintype "passive"))
      (node (ref "R16") (pin "1") (pinfunction "1_1") (pintype "passive"))
      (node (ref "U5") (pin "16") (pinfunction "ADDR_16") (pintype "input"))
    )
    (net (code "71") (name "Net-(U6-VSEL)") (class "Default")
      (node (ref "R22") (pin "2") (pinfunction "2_2") (pintype "passive"))
      (node (ref "R23") (pin "1") (pinfunction "1_1") (pintype "passive"))
      (node (ref "U6") (pin "8") (pinfunction "VSEL_8") (pintype "power_in"))
    )
    (net (code "72") (name "Net-(U7-AREF)") (class "Default")
      (node (ref "C36") (pin "1") (pinfunction "1_1") (pintype "passive"))
      (node (ref "U7") (pin "20") (pinfunction "AREF_20") (pintype "passive"))
    )
    (net (code "73") (name "Net-(U9-CT)") (class "Default")
      (node (ref "R31") (pin "1") (pinfunction "1_1") (pintype "passive"))
      (node (ref "U9") (pin "6") (pinfunction "CT_6") (pintype "passive"))
    )
    (net (code "74") (name "Net-(U10-CT)") (class "Default")
      (node (ref "R34") (pin "1") (pinfunction "1_1") (pintype "passive"))
      (node (ref "U10") (pin "6") (pinfunction "CT_6") (pintype "passive"))
    )
    (net (code "75") (name "Net-(U11-CT)") (class "Default")
      (node (ref "R37") (pin "1") (pinfunction "1_1") (pintype "passive"))
      (node (ref "U11") (pin "6") (pinfunction "CT_6") (pintype "passive"))
    )
    (net (code "76") (name "Net-(U13-VSEL)") (class "Default")
      (node (ref "R42") (pin "2") (pinfunction "2_2") (pintype "passive"))
      (node (ref "R43") (pin "1") (pinfunction "1_1") (pintype "passive"))
      (node (ref "U13") (pin "8") (pinfunction "VSEL_8") (pintype "power_in"))
    )
    (net (code "77") (name "Net-(U14-4.ADDR)") (class "Default")
      (node (ref "R47") (pin "1") (pinfunction "1_1") (pintype "passive"))
      (node (ref "R48") (pin "1") (pinfunction "1_1") (pintype "passive"))
      (node (ref "U14") (pin "4") (pinfunction "4.ADDR_4") (pintype "bidirectional"))
    )
    (net (code "78") (name "Net-(U15-1.OUT)") (class "Default")
      (node (ref "R46") (pin "1") (pinfunction "1_1") (pintype "passive"))
      (node (ref "U15") (pin "1") (pinfunction "1.OUT_1") (pintype "bidirectional"))
    )
    (net (code "79") (name "Net-(U16-4.ADDR)") (class "Default")
      (node (ref "R51") (pin "1") (pinfunction "1_1") (pintype "passive"))
      (node (ref "R52") (pin "1") (pinfunction "1_1") (pintype "passive"))
      (node (ref "U16") (pin "4") (pinfunction "4.ADDR_4") (pintype "bidirectional"))
    )
    (net (code "80") (name "Net-(U17-1.OUT)") (class "Default")
      (node (ref "R50") (pin "1") (pinfunction "1_1") (pintype "passive"))
      (node (ref "U17") (pin "1") (pinfunction "1.OUT_1") (pintype "bidirectional"))
    )
    (net (code "81") (name "Net-(U18-SPLIT)") (class "Default")
      (node (ref "R55") (pin "1") (pinfunction "1_1") (pintype "passive"))
      (node (ref "U18") (pin "5") (pinfunction "SPLIT_5") (pintype "passive"))
    )
    (net (code "82") (name "PB0") (class "Default")
      (node (ref "U7") (pin "12") (pinfunction "PB0_12") (pintype "bidirectional"))
    )
    (net (code "83") (name "PB1") (class "Default")
      (node (ref "U7") (pin "13") (pinfunction "PB1_13") (pintype "bidirectional"))
    )
    (net (code "84") (name "PB2") (class "Default")
      (node (ref "U7") (pin "14") (pinfunction "PB2_14") (pintype "bidirectional"))
    )
    (net (code "85") (name "PC0") (class "Default")
      (node (ref "U7") (pin "23") (pinfunction "PC0_23") (pintype "bidirectional"))
    )
    (net (code "86") (name "PC1") (class "Default")
      (node (ref "U7") (pin "24") (pinfunction "PC1_24") (pintype "bidirectional"))
    )
    (net (code "87") (name "PC2") (class "Default")
      (node (ref "U7") (pin "25") (pinfunction "PC2_25") (pintype "bidirectional"))
    )
    (net (code "88") (name "PC3") (class "Default")
      (node (ref "U7") (pin "26") (pinfunction "PC3_26") (pintype "bidirectional"))
    )
    (net (code "89") (name "PD2") (class "Default")
      (node (ref "U7") (pin "32") (pinfunction "PD2_32") (pintype "bidirectional"))
    )
    (net (code "90") (name "PD3") (class "Default")
      (node (ref "U7") (pin "1") (pinfunction "PD3_1") (pintype "bidirectional"))
    )
    (net (code "91") (name "PD4") (class "Default")
      (node (ref "R30") (pin "1") (pinfunction "1_1") (pintype "passive"))
      (node (ref "U7") (pin "2") (pinfunction "PD4_2") (pintype "bidirectional"))
    )
    (net (code "92") (name "PDIS") (class "Default")
      (node (ref "R12") (pin "1") (pinfunction "1_1") (pintype "passive"))
      (node (ref "R24") (pin "1") (pinfunction "1_1") (pintype "passive"))
      (node (ref "R44") (pin "1") (pinfunction "1_1") (pintype "passive"))
      (node (ref "U13") (pin "1") (pinfunction "PDIS_1") (pintype "power_in"))
      (node (ref "U3") (pin "1") (pinfunction "PDIS_1") (pintype "power_in"))
      (node (ref "U6") (pin "1") (pinfunction "PDIS_1") (pintype "power_in"))
    )
    (net (code "93") (name "SCL") (class "Default")
      (node (ref "U12") (pin "3") (pinfunction "SCL1_3") (pintype "input"))
      (node (ref "U16") (pin "5") (pinfunction "5.SCL_5") (pintype "bidirectional"))
      (node (ref "U2") (pin "3") (pinfunction "SCL1_3") (pintype "input"))
      (node (ref "U4") (pin "3") (pinfunction "SCL1_3") (pintype "input"))
      (node (ref "U7") (pin "28") (pinfunction "PC5_28") (pintype "bidirectional"))
    )
    (net (code "94") (name "SDA") (class "Default")
      (node (ref "U12") (pin "2") (pinfunction "SDA1_2") (pintype "bidirectional"))
      (node (ref "U16") (pin "6") (pinfunction "6.SDA_6") (pintype "bidirectional"))
      (node (ref "U2") (pin "2") (pinfunction "SDA1_2") (pintype "bidirectional"))
      (node (ref "U4") (pin "2") (pinfunction "SDA1_2") (pintype "bidirectional"))
      (node (ref "U7") (pin "27") (pinfunction "PC4_27") (pintype "bidirectional"))
    )
    (net (code "95") (name "V+") (class "Default")
      (node (ref "J5") (pin "1") (pinfunction "1_1") (pintype "bidirectional"))
      (node (ref "J6") (pin "1") (pinfunction "1_1") (pintype "bidirectional"))
      (node (ref "K1") (pin "14.1") (pinfunction "14_14.1") (pintype "passive"))
      (node (ref "K1") (pin "14.2") (pinfunction "14_14.2") (pintype "passive"))
      (node (ref "R34") (pin "2") (pinfunction "2_2") (pintype "passive"))
      (node (ref "R37") (pin "2") (pinfunction "2_2") (pintype "passive"))
    )
    (net (code "96") (name "VBUS") (class "Default")
      (node (ref "J9") (pin "4") (pinfunction "4_4") (pintype "bidirectional"))
    )
    (net (code "97") (name "VDD") (class "Default")
      (node (ref "C10") (pin "1") (pinfunction "+_1") (pintype "passive"))
      (node (ref "C11") (pin "1ASD") (pinfunction "+_1ASD") (pintype "passive"))
      (node (ref "C12") (pin "1") (pinfunction "+_1") (pintype "passive"))
      (node (ref "C13") (pin "1ASD") (pinfunction "+_1ASD") (pintype "passive"))
      (node (ref "C18") (pin "1") (pinfunction "+_1") (pintype "passive"))
      (node (ref "C19") (pin "1ASD") (pinfunction "+_1ASD") (pintype "passive"))
      (node (ref "C22") (pin "1") (pinfunction "+_1") (pintype "passive"))
      (node (ref "C23") (pin "1") (pinfunction "+_1") (pintype "passive"))
      (node (ref "C25") (pin "1ASD") (pinfunction "+_1ASD") (pintype "passive"))
      (node (ref "C32") (pin "1") (pinfunction "+_1") (pintype "passive"))
      (node (ref "C33") (pin "1") (pinfunction "+_1") (pintype "passive"))
      (node (ref "C39") (pin "1") (pinfunction "+_1") (pintype "passive"))
      (node (ref "C40") (pin "1ASD") (pinfunction "+_1ASD") (pintype "passive"))
      (node (ref "C43") (pin "1") (pinfunction "+_1") (pintype "passive"))
      (node (ref "C44") (pin "1") (pinfunction "+_1") (pintype "passive"))
      (node (ref "C46") (pin "1ASD") (pinfunction "+_1ASD") (pintype "passive"))
      (node (ref "C53") (pin "1") (pinfunction "+_1") (pintype "passive"))
      (node (ref "C54") (pin "1") (pinfunction "+_1") (pintype "passive"))
      (node (ref "C55") (pin "1") (pinfunction "+_1") (pintype "passive"))
      (node (ref "C56") (pin "1") (pinfunction "+_1") (pintype "passive"))
      (node (ref "C58") (pin "1") (pinfunction "+_1") (pintype "passive"))
      (node (ref "C59") (pin "1") (pinfunction "+_1") (pintype "passive"))
      (node (ref "C9") (pin "1") (pinfunction "+_1") (pintype "passive"))
      (node (ref "J3") (pin "2") (pinfunction "2_2") (pintype "bidirectional"))
      (node (ref "R12") (pin "2") (pinfunction "2_2") (pintype "passive"))
      (node (ref "R24") (pin "2") (pinfunction "2_2") (pintype "passive"))
      (node (ref "R25") (pin "1") (pinfunction "1_1") (pintype "passive"))
      (node (ref "R26") (pin "1") (pinfunction "1_1") (pintype "passive"))
      (node (ref "R29") (pin "1") (pinfunction "1_1") (pintype "passive"))
      (node (ref "R33") (pin "2") (pinfunction "2_2") (pintype "passive"))
      (node (ref "R36") (pin "2") (pinfunction "2_2") (pintype "passive"))
      (node (ref "R39") (pin "2") (pinfunction "2_2") (pintype "passive"))
      (node (ref "R44") (pin "2") (pinfunction "2_2") (pintype "passive"))
      (node (ref "R51") (pin "2") (pinfunction "2_2") (pintype "passive"))
      (node (ref "U12") (pin "1") (pinfunction "VDD1_1") (pintype "power_in"))
      (node (ref "U13") (pin "3") (pinfunction "VDDP_3") (pintype "bidirectional"))
      (node (ref "U16") (pin "1") (pinfunction "1.VA_1") (pintype "bidirectional"))
      (node (ref "U17") (pin "6") (pinfunction "6.VS_6") (pintype "bidirectional"))
      (node (ref "U18") (pin "3") (pinfunction "VDD_3") (pintype "power_in"))
      (node (ref "U2") (pin "1") (pinfunction "VDD1_1") (pintype "power_in"))
      (node (ref "U3") (pin "3") (pinfunction "VDDP_3") (pintype "bidirectional"))
      (node (ref "U4") (pin "1") (pinfunction "VDD1_1") (pintype "power_in"))
      (node (ref "U6") (pin "3") (pinfunction "VDDP_3") (pintype "bidirectional"))
      (node (ref "U7") (pin "4") (pinfunction "VCC_2_4") (pintype "power_in"))
      (node (ref "U7") (pin "6") (pinfunction "VCC_6") (pintype "power_in"))
    )
    (net (code "98") (name "VISO2") (class "Default")
      (node (ref "C38") (pin "1") (pinfunction "+_1") (pintype "passive"))
      (node (ref "C41") (pin "1") (pinfunction "+_1") (pintype "passive"))
      (node (ref "C42") (pin "1") (pinfunction "+_1") (pintype "passive"))
      (node (ref "C45") (pin "1ASD") (pinfunction "+_1ASD") (pintype "passive"))
      (node (ref "C48") (pin "1") (pinfunction "+_1") (pintype "passive"))
      (node (ref "C49") (pin "1") (pinfunction "+_1") (pintype "passive"))
      (node (ref "C50") (pin "1") (pinfunction "+_1") (pintype "passive"))
      (node (ref "C51") (pin "1") (pinfunction "+_1") (pintype "passive"))
      (node (ref "FL10") (pin "1") (pinfunction "1_1") (pintype "passive"))
      (node (ref "R40") (pin "2") (pinfunction "2_2") (pintype "passive"))
      (node (ref "R41") (pin "2") (pinfunction "2_2") (pintype "passive"))
      (node (ref "R43") (pin "2") (pinfunction "2_2") (pintype "passive"))
      (node (ref "R47") (pin "2") (pinfunction "2_2") (pintype "passive"))
      (node (ref "U12") (pin "8") (pinfunction "VDD2_8") (pintype "power_in"))
      (node (ref "U14") (pin "1") (pinfunction "1.VA_1") (pintype "bidirectional"))
      (node (ref "U15") (pin "6") (pinfunction "6.VS_6") (pintype "bidirectional"))
    )
    (net (code "99") (name "XTAL1") (class "Default")
      (node (ref "C27") (pin "2") (pinfunction "+_2") (pintype "passive"))
      (node (ref "U7") (pin "7") (pinfunction "PB6_7") (pintype "bidirectional"))
      (node (ref "Y1") (pin "3") (pinfunction "2_3") (pintype "bidirectional"))
    )
    (net (code "100") (name "XTAL2") (class "Default")
      (node (ref "C28") (pin "2") (pinfunction "+_2") (pintype "passive"))
      (node (ref "U7") (pin "8") (pinfunction "PB7_8") (pintype "bidirectional"))
      (node (ref "Y1") (pin "1") (pinfunction "1_1") (pintype "bidirectional"))
    )
    (net (code "101") (name "unconnected-(J8-PadRING_SW)") (class "Default")
      (node (ref "J8") (pin "RING_SW") (pinfunction "RING_SW_RING_SW") (pintype "bidirectional"))
    )
    (net (code "102") (name "unconnected-(J8-PadTIP)") (class "Default")
      (node (ref "J8") (pin "TIP") (pinfunction "TIP_TIP") (pintype "bidirectional"))
    )
    (net (code "103") (name "unconnected-(U1-ALERT_1-Pad11)") (class "Default")
      (node (ref "U1") (pin "11") (pinfunction "ALERT_1_11") (pintype "output"))
    )
    (net (code "104") (name "unconnected-(U1-ALERT_2-Pad12)") (class "Default")
      (node (ref "U1") (pin "12") (pinfunction "ALERT_2_12") (pintype "output"))
    )
    (net (code "105") (name "unconnected-(U1-ALERT_3-Pad14)") (class "Default")
      (node (ref "U1") (pin "14") (pinfunction "ALERT_3_14") (pintype "output"))
    )
    (net (code "106") (name "unconnected-(U1-ALERT_4-Pad15)") (class "Default")
      (node (ref "U1") (pin "15") (pinfunction "ALERT_4_15") (pintype "output"))
    )
    (net (code "107") (name "unconnected-(U5-ALERT_1-Pad11)") (class "Default")
      (node (ref "U5") (pin "11") (pinfunction "ALERT_1_11") (pintype "output"))
    )
    (net (code "108") (name "unconnected-(U5-ALERT_2-Pad12)") (class "Default")
      (node (ref "U5") (pin "12") (pinfunction "ALERT_2_12") (pintype "output"))
    )
    (net (code "109") (name "unconnected-(U5-ALERT_3-Pad14)") (class "Default")
      (node (ref "U5") (pin "14") (pinfunction "ALERT_3_14") (pintype "output"))
    )
    (net (code "110") (name "unconnected-(U5-ALERT_4-Pad15)") (class "Default")
      (node (ref "U5") (pin "15") (pinfunction "ALERT_4_15") (pintype "output"))
    )
    (net (code "111") (name "unconnected-(U12-GND2-Pad5)") (class "Default")
      (node (ref "U12") (pin "5") (pinfunction "GND2_5") (pintype "passive"))
    )
  )
)
